# LARIX_V5.net
KiCad netlist of a schematic drawn in EAGLE
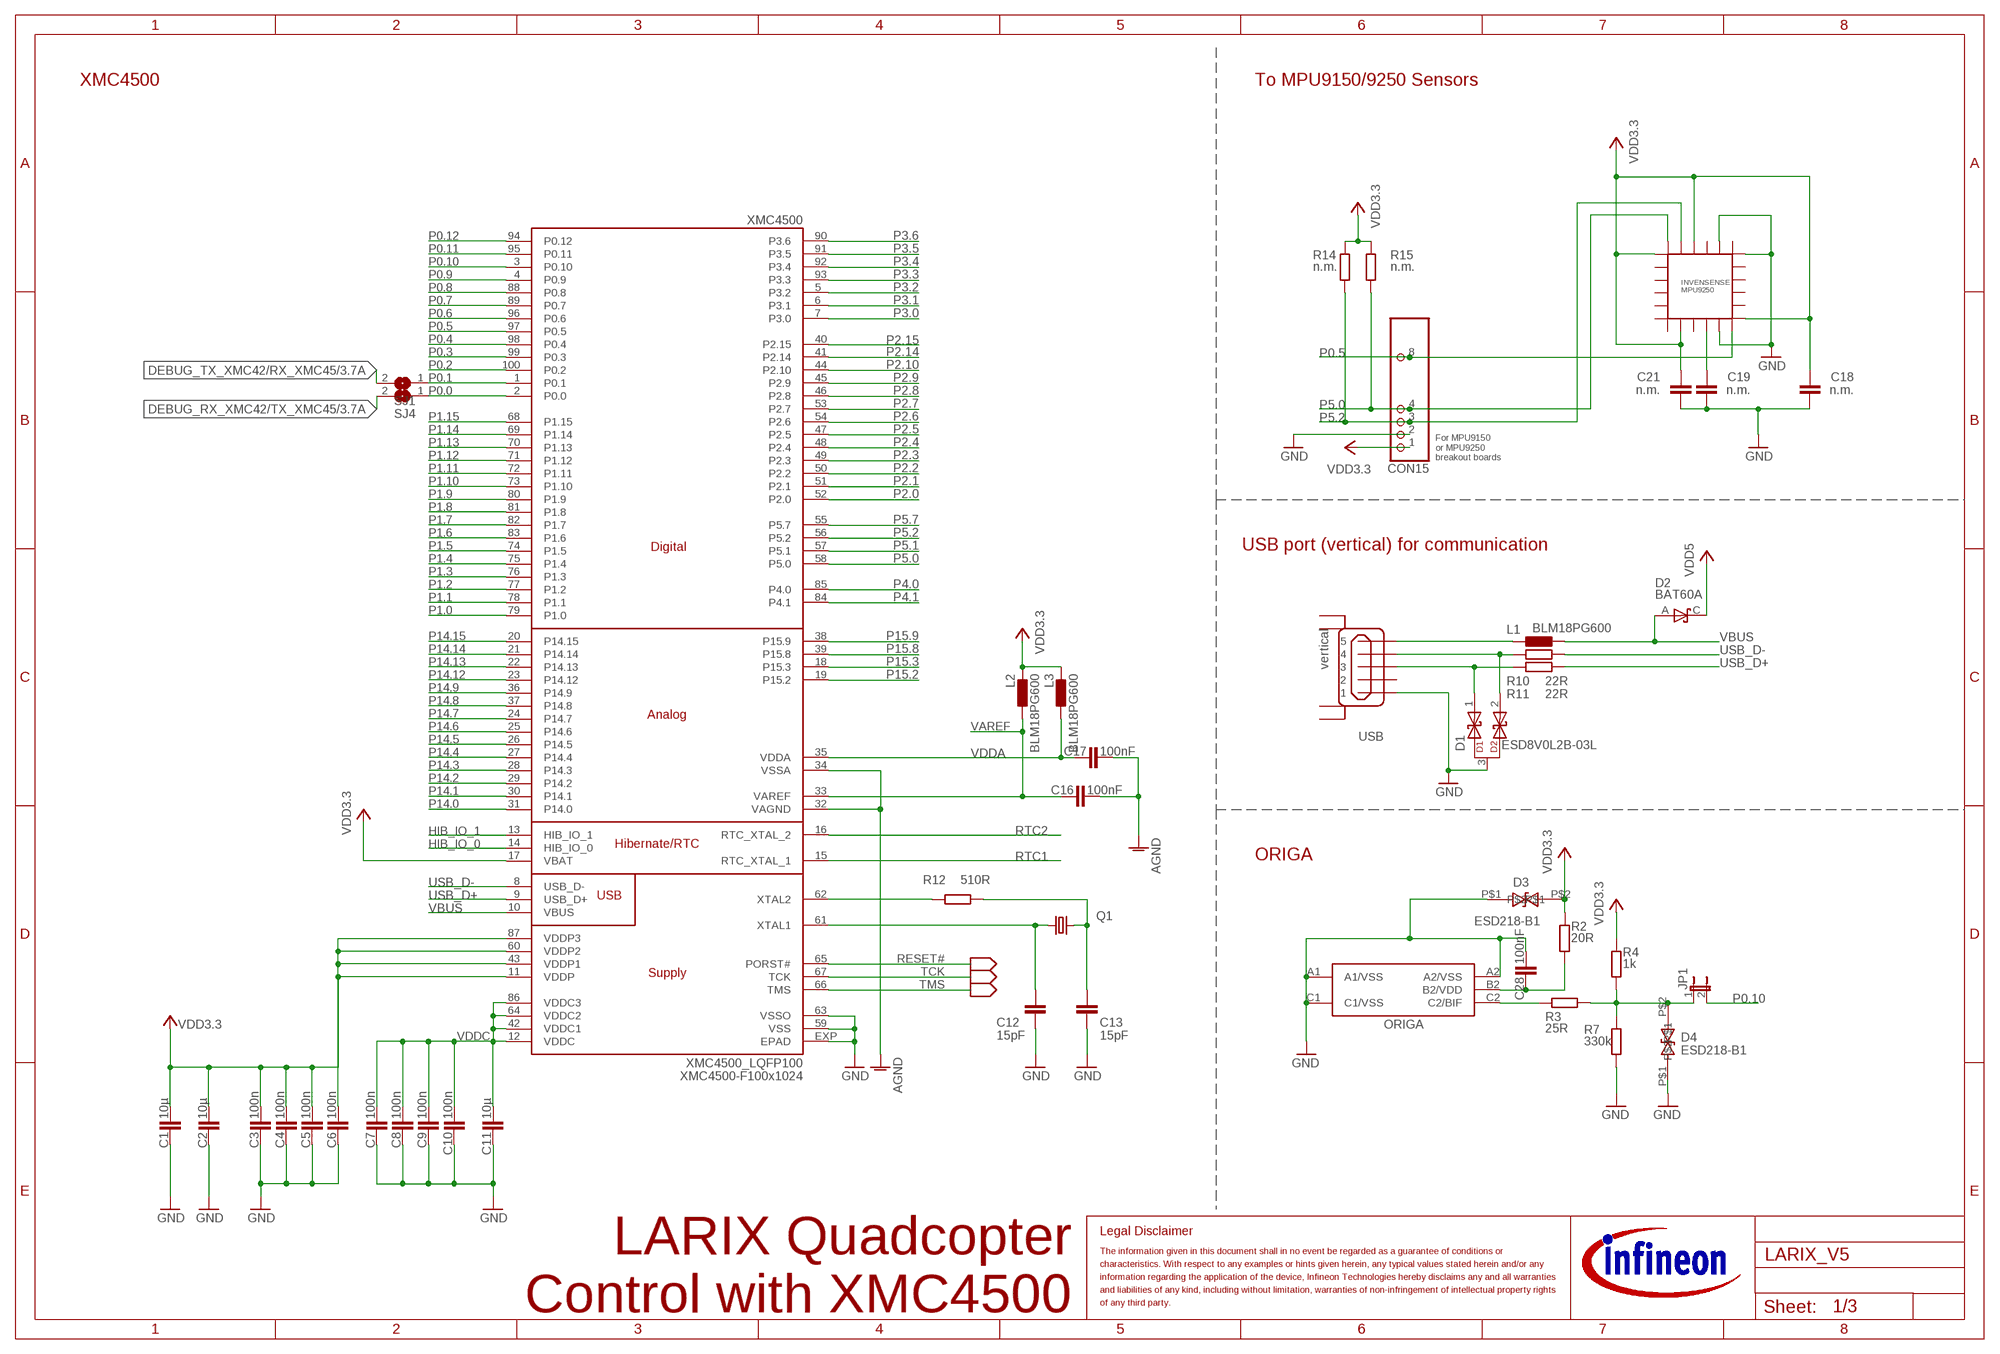
[diagram p0: schematic, sheet 1]
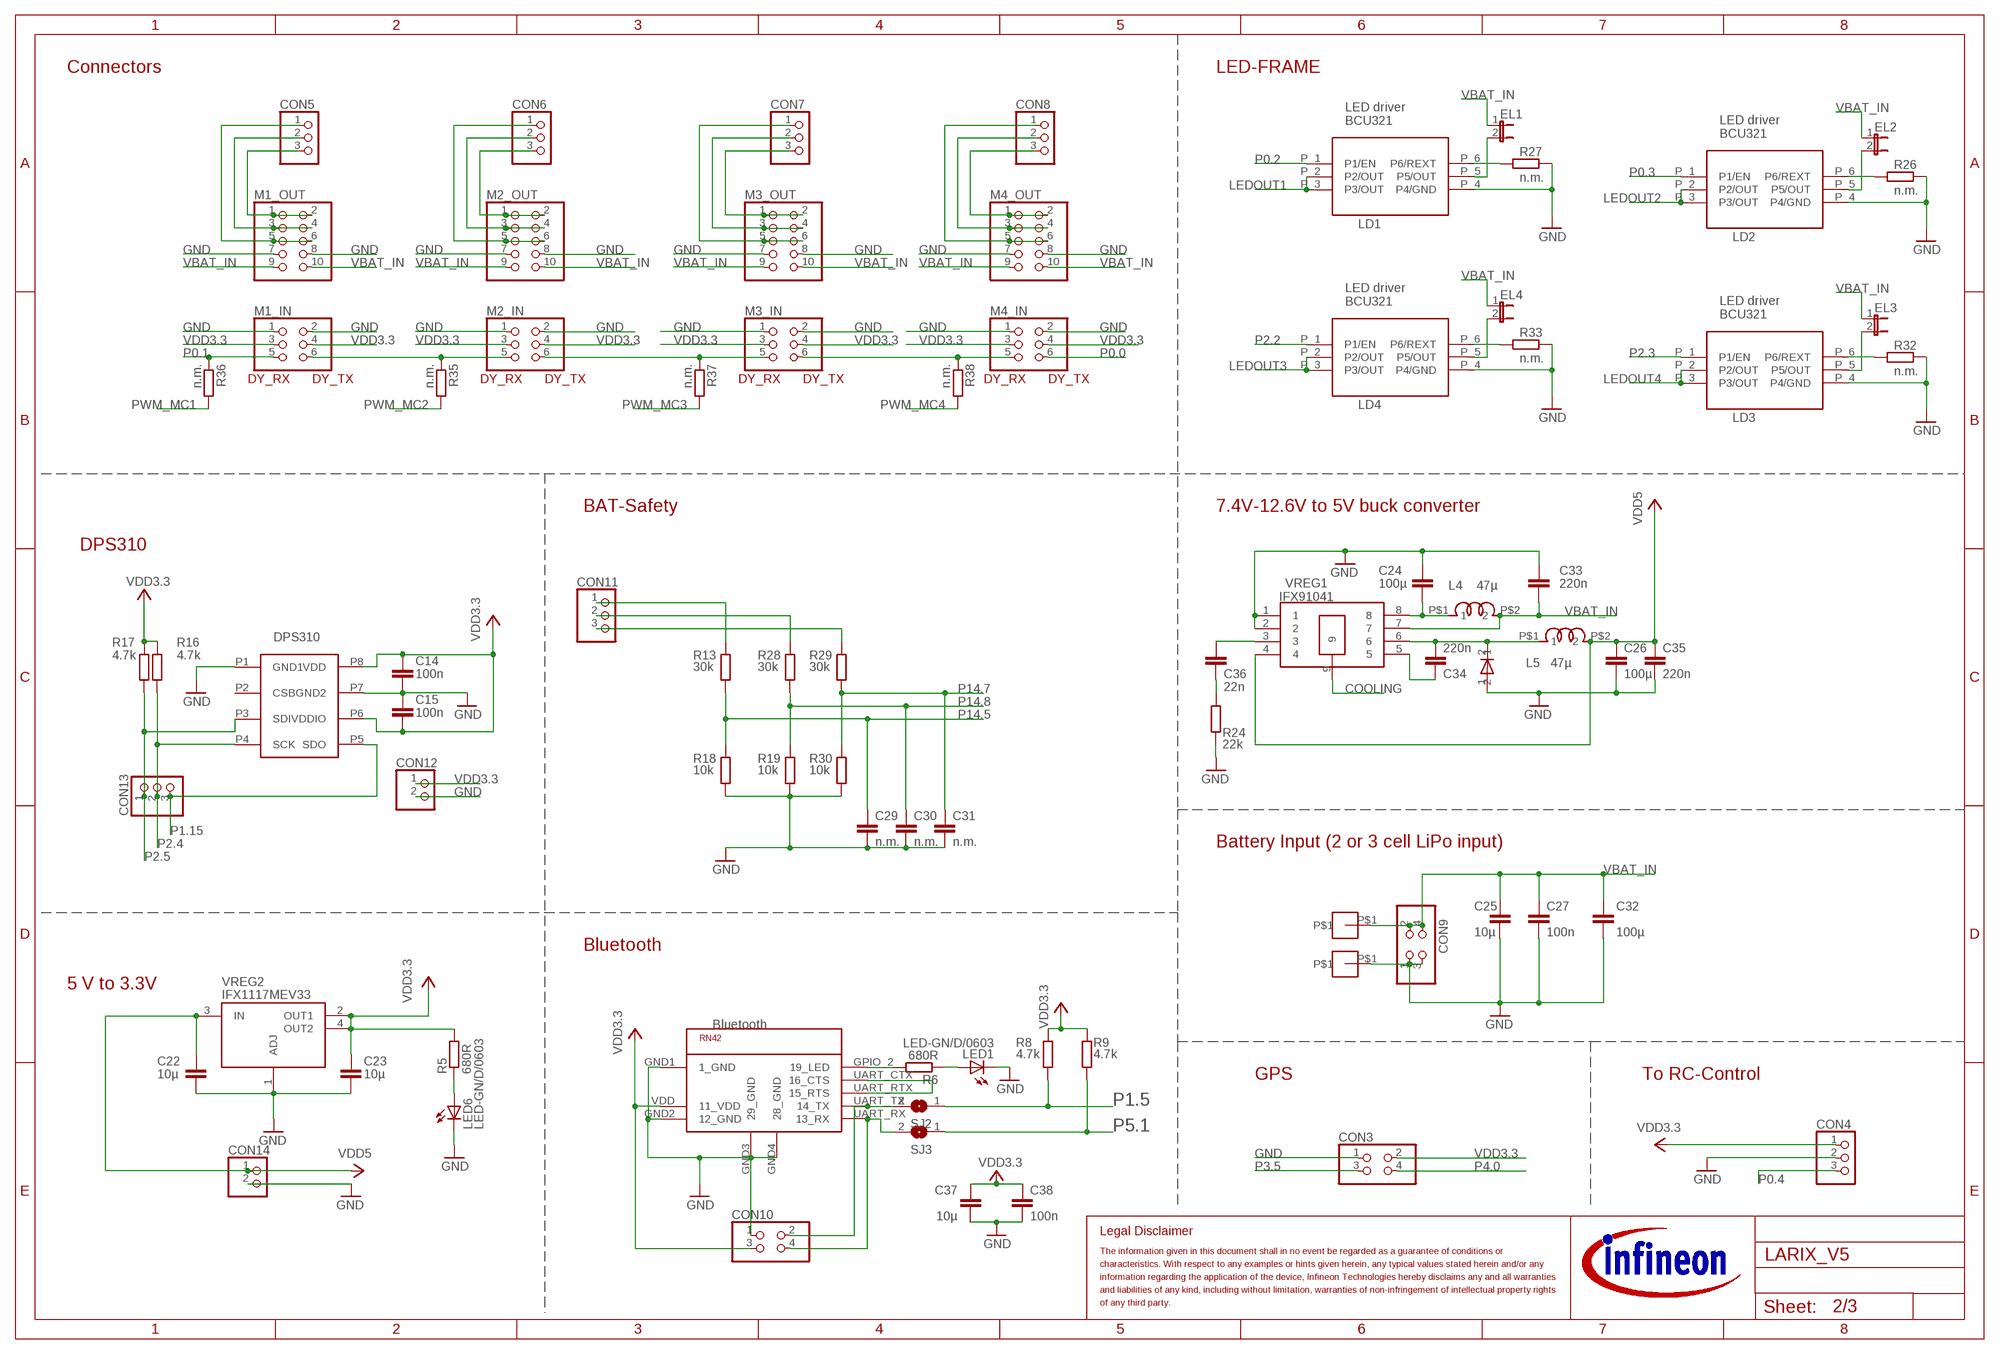
[diagram p1: schematic, sheet 2]
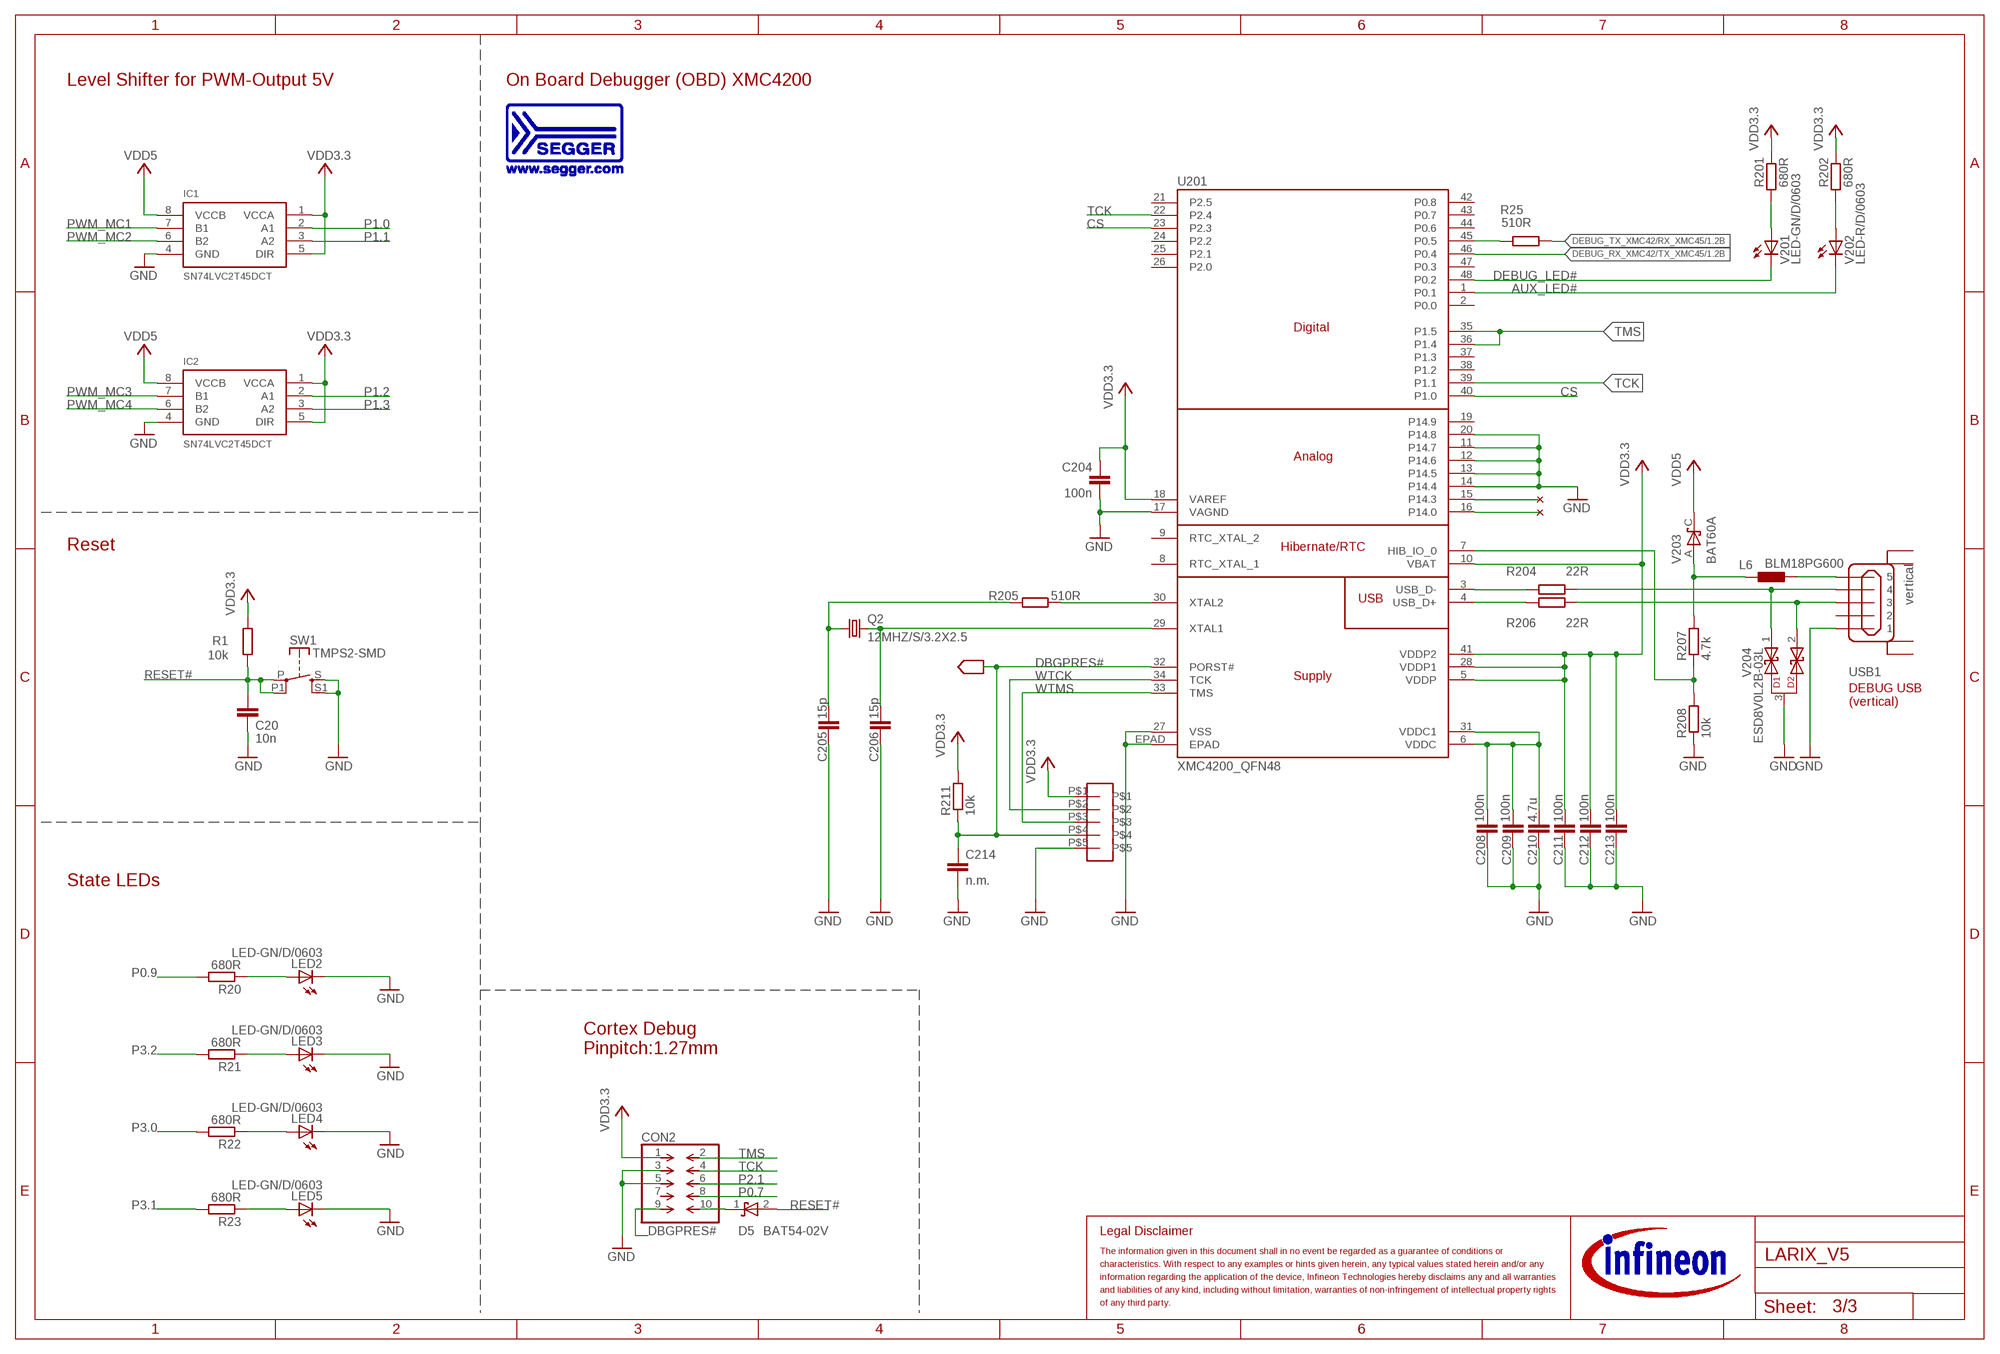
[diagram p2: schematic, sheet 3]

(export (version "E")
  (design (tool "Eeschema 10.0.6"))
  (components
    (comp (ref "C1")
      (value "10µ")
      (footprint "eagle-import:C0805K")
      (libsource (lib "eagle-import") (part "C-EUC0805K"))
    )
    (comp (ref "C2")
      (value "10µ")
      (footprint "eagle-import:C0805K")
      (libsource (lib "eagle-import") (part "C-EUC0805K"))
    )
    (comp (ref "C3")
      (value "100n")
      (footprint "eagle-import:C0603")
      (libsource (lib "eagle-import") (part "resistor_C-EUC0603"))
    )
    (comp (ref "C4")
      (value "100n")
      (footprint "eagle-import:C0603")
      (libsource (lib "eagle-import") (part "resistor_C-EUC0603"))
    )
    (comp (ref "C5")
      (value "100n")
      (footprint "eagle-import:C0603")
      (libsource (lib "eagle-import") (part "resistor_C-EUC0603"))
    )
    (comp (ref "C6")
      (value "100n")
      (footprint "eagle-import:C0603")
      (libsource (lib "eagle-import") (part "resistor_C-EUC0603"))
    )
    (comp (ref "C7")
      (value "100n")
      (footprint "eagle-import:C0603")
      (libsource (lib "eagle-import") (part "resistor_C-EUC0603"))
    )
    (comp (ref "C8")
      (value "100n")
      (footprint "eagle-import:C0603")
      (libsource (lib "eagle-import") (part "resistor_C-EUC0603"))
    )
    (comp (ref "C9")
      (value "100n")
      (footprint "eagle-import:C0603")
      (libsource (lib "eagle-import") (part "resistor_C-EUC0603"))
    )
    (comp (ref "C10")
      (value "100n")
      (footprint "eagle-import:C0603")
      (libsource (lib "eagle-import") (part "resistor_C-EUC0603"))
    )
    (comp (ref "C11")
      (value "10µ")
      (footprint "eagle-import:C0805K")
      (libsource (lib "eagle-import") (part "C-EUC0805K"))
    )
    (comp (ref "C12")
      (value "15pF")
      (footprint "eagle-import:C0603")
      (libsource (lib "eagle-import") (part "resistor_C-EUC0603"))
    )
    (comp (ref "C13")
      (value "15pF")
      (footprint "eagle-import:C0603")
      (libsource (lib "eagle-import") (part "resistor_C-EUC0603"))
    )
    (comp (ref "C16")
      (value "100nF")
      (footprint "eagle-import:C0603")
      (libsource (lib "eagle-import") (part "resistor_C-EUC0603"))
    )
    (comp (ref "C17")
      (value "100nF")
      (footprint "eagle-import:C0603")
      (libsource (lib "eagle-import") (part "resistor_C-EUC0603"))
    )
    (comp (ref "C18")
      (value "n.m.")
      (footprint "eagle-import:C0603")
      (libsource (lib "eagle-import") (part "resistor_C-EUC0603"))
    )
    (comp (ref "C19")
      (value "n.m.")
      (footprint "eagle-import:C0603")
      (libsource (lib "eagle-import") (part "resistor_C-EUC0603"))
    )
    (comp (ref "C21")
      (value "n.m.")
      (footprint "eagle-import:C0603")
      (libsource (lib "eagle-import") (part "resistor_C-EUC0603"))
    )
    (comp (ref "C28")
      (value "100nF")
      (footprint "eagle-import:C0603")
      (libsource (lib "eagle-import") (part "resistor_C-EUC0603"))
    )
    (comp (ref "CON15")
      (value "PINHD-1X10")
      (footprint "eagle-import:1X10")
      (libsource (lib "eagle-import") (part "PINHD-1X10"))
    )
    (comp (ref "D1")
      (value "ESD8V0L2B-03L")
      (footprint "eagle-import:TSLP-3-1")
      (libsource (lib "eagle-import") (part "ESD8V0L2B-03L"))
    )
    (comp (ref "D2")
      (value "BAT60A")
      (footprint "eagle-import:SOD323-R")
      (libsource (lib "eagle-import") (part "XMC4500_Relax-V1+USBvertical_BAT60"))
    )
    (comp (ref "D3")
      (value "ESD218-B1-02EL")
      (footprint "eagle-import:TSLP-2-20")
      (libsource (lib "eagle-import") (part "ESD218-B1-02EL"))
    )
    (comp (ref "D4")
      (value "ESD218-B1-02EL")
      (footprint "eagle-import:TSLP-2-20")
      (libsource (lib "eagle-import") (part "ESD218-B1-02EL"))
    )
    (comp (ref "JP1")
      (value "JP1E")
      (footprint "eagle-import:JP1")
      (libsource (lib "eagle-import") (part "JP1E"))
    )
    (comp (ref "L1")
      (value "BLM18PG600")
      (footprint "eagle-import:L1608")
      (libsource (lib "eagle-import") (part "L_EU_L0603"))
    )
    (comp (ref "L2")
      (value "BLM18PG600")
      (footprint "eagle-import:L1608")
      (libsource (lib "eagle-import") (part "L_EU_L0603"))
    )
    (comp (ref "L3")
      (value "BLM18PG600")
      (footprint "eagle-import:L1608")
      (libsource (lib "eagle-import") (part "L_EU_L0603"))
    )
    (comp (ref "MPU9250")
      (value "INVENSENSE9250EHERBY")
      (footprint "eagle-import:QFN3X3-24+")
      (libsource (lib "eagle-import") (part "INVENSENSE9250HERBYE"))
    )
    (comp (ref "ORIGA")
      (value "ORIGA2L")
      (footprint "eagle-import:WLB-5")
      (libsource (lib "eagle-import") (part "ORIGA2L"))
    )
    (comp (ref "Q1")
      (value "12MHZ/S/3.2X2.5")
      (footprint "eagle-import:32X25_4PAD")
      (libsource (lib "eagle-import") (part "NX3225_2"))
    )
    (comp (ref "R2")
      (value "20R")
      (footprint "eagle-import:R0603")
      (libsource (lib "eagle-import") (part "R-EU_R0603"))
    )
    (comp (ref "R3")
      (value "25R")
      (footprint "eagle-import:R0603")
      (libsource (lib "eagle-import") (part "R-EU_R0603"))
    )
    (comp (ref "R4")
      (value "1k")
      (footprint "eagle-import:R0603")
      (libsource (lib "eagle-import") (part "R-EU_R0603"))
    )
    (comp (ref "R7")
      (value "330k")
      (footprint "eagle-import:R0603")
      (libsource (lib "eagle-import") (part "R-EU_R0603"))
    )
    (comp (ref "R10")
      (value "22R")
      (footprint "eagle-import:R0603")
      (libsource (lib "eagle-import") (part "resistor_R-EU_R0603"))
    )
    (comp (ref "R11")
      (value "22R")
      (footprint "eagle-import:R0603")
      (libsource (lib "eagle-import") (part "resistor_R-EU_R0603"))
    )
    (comp (ref "R12")
      (value "510R")
      (footprint "eagle-import:R0603")
      (libsource (lib "eagle-import") (part "R-EU_R0603"))
    )
    (comp (ref "R14")
      (value "n.m.")
      (footprint "eagle-import:R0603")
      (libsource (lib "eagle-import") (part "resistor_R-EU_R0603"))
    )
    (comp (ref "R15")
      (value "n.m.")
      (footprint "eagle-import:R0603")
      (libsource (lib "eagle-import") (part "resistor_R-EU_R0603"))
    )
    (comp (ref "SJ1") (value "SJ") (footprint "eagle-import:SJ") (libsource (lib "eagle-import") (part "SJ")))
    (comp (ref "SJ4") (value "SJ") (footprint "eagle-import:SJ") (libsource (lib "eagle-import") (part "SJ")))
    (comp (ref "USB")
      (value "vertical")
      (footprint "eagle-import:USBVERTICAL")
      (libsource (lib "eagle-import") (part "MICRO_USB_VERTICAL"))
    )
    (comp (ref "XMC4500")
      (value "XMC4500_LQFP100")
      (footprint "eagle-import:P_PG-LQFP-100-11")
      (libsource (lib "eagle-import") (part "XMC4400_LQFP100"))
    )
    (comp (ref "C14")
      (value "100n")
      (footprint "eagle-import:C0603")
      (libsource (lib "eagle-import") (part "resistor_C-EUC0603"))
    )
    (comp (ref "C15")
      (value "100n")
      (footprint "eagle-import:C0603")
      (libsource (lib "eagle-import") (part "resistor_C-EUC0603"))
    )
    (comp (ref "C22")
      (value "10µ")
      (footprint "eagle-import:C0805K")
      (libsource (lib "eagle-import") (part "C-EUC0805K"))
    )
    (comp (ref "C23")
      (value "10µ")
      (footprint "eagle-import:C0805K")
      (libsource (lib "eagle-import") (part "C-EUC0805K"))
    )
    (comp (ref "C24")
      (value "100µ")
      (footprint "eagle-import:C1210")
      (libsource (lib "eagle-import") (part "resistor_C-EUC1210"))
    )
    (comp (ref "C25")
      (value "10µ")
      (footprint "eagle-import:C0805K")
      (libsource (lib "eagle-import") (part "C-EUC0805K"))
    )
    (comp (ref "C26")
      (value "100µ")
      (footprint "eagle-import:C1210")
      (libsource (lib "eagle-import") (part "resistor_C-EUC1210"))
    )
    (comp (ref "C27")
      (value "100n")
      (footprint "eagle-import:C0603")
      (libsource (lib "eagle-import") (part "resistor_C-EUC0603"))
    )
    (comp (ref "C29")
      (value "n.m.")
      (footprint "eagle-import:C0603")
      (libsource (lib "eagle-import") (part "resistor_C-EUC0603"))
    )
    (comp (ref "C30")
      (value "n.m.")
      (footprint "eagle-import:C0603")
      (libsource (lib "eagle-import") (part "resistor_C-EUC0603"))
    )
    (comp (ref "C31")
      (value "n.m.")
      (footprint "eagle-import:C0603")
      (libsource (lib "eagle-import") (part "resistor_C-EUC0603"))
    )
    (comp (ref "C32")
      (value "100µ")
      (footprint "eagle-import:C1210")
      (libsource (lib "eagle-import") (part "resistor_C-EUC1210"))
    )
    (comp (ref "C33")
      (value "220n")
      (footprint "eagle-import:C0603")
      (libsource (lib "eagle-import") (part "resistor_C-EUC0603"))
    )
    (comp (ref "C34")
      (value "220n")
      (footprint "eagle-import:C0603")
      (libsource (lib "eagle-import") (part "resistor_C-EUC0603"))
    )
    (comp (ref "C35")
      (value "220n")
      (footprint "eagle-import:C0603")
      (libsource (lib "eagle-import") (part "resistor_C-EUC0603"))
    )
    (comp (ref "C36")
      (value "22n")
      (footprint "eagle-import:C0603")
      (libsource (lib "eagle-import") (part "resistor_C-EUC0603"))
    )
    (comp (ref "C37")
      (value "10µ")
      (footprint "eagle-import:C0805K")
      (libsource (lib "eagle-import") (part "C-EUC0805K"))
    )
    (comp (ref "C38")
      (value "100n")
      (footprint "eagle-import:C0603")
      (libsource (lib "eagle-import") (part "resistor_C-EUC0603"))
    )
    (comp (ref "CON3")
      (value "PINHD-2X2")
      (footprint "eagle-import:2X02")
      (libsource (lib "eagle-import") (part "PINHD-2X2"))
    )
    (comp (ref "CON4")
      (value "PINHD-1X3")
      (footprint "eagle-import:1X03")
      (libsource (lib "eagle-import") (part "PINHD-1X3"))
    )
    (comp (ref "CON5")
      (value "PINHD-1X3")
      (footprint "eagle-import:1X03")
      (libsource (lib "eagle-import") (part "PINHD-1X3"))
    )
    (comp (ref "CON6")
      (value "PINHD-1X3")
      (footprint "eagle-import:1X03")
      (libsource (lib "eagle-import") (part "PINHD-1X3"))
    )
    (comp (ref "CON7")
      (value "PINHD-1X3")
      (footprint "eagle-import:1X03")
      (libsource (lib "eagle-import") (part "PINHD-1X3"))
    )
    (comp (ref "CON8")
      (value "PINHD-1X3")
      (footprint "eagle-import:1X03")
      (libsource (lib "eagle-import") (part "PINHD-1X3"))
    )
    (comp (ref "CON9")
      (value "PINHD-2X2")
      (footprint "eagle-import:2X02")
      (libsource (lib "eagle-import") (part "PINHD-2X2"))
    )
    (comp (ref "CON10")
      (value "PINHD-2X2")
      (footprint "eagle-import:2X02")
      (libsource (lib "eagle-import") (part "PINHD-2X2"))
    )
    (comp (ref "CON11")
      (value "PINHD-1X3")
      (footprint "eagle-import:1X03")
      (libsource (lib "eagle-import") (part "PINHD-1X3"))
    )
    (comp (ref "CON12")
      (value "PINHD-1X2")
      (footprint "eagle-import:1X02")
      (libsource (lib "eagle-import") (part "PINHD-1X2"))
    )
    (comp (ref "CON13")
      (value "PINHD-1X3")
      (footprint "eagle-import:1X03")
      (libsource (lib "eagle-import") (part "PINHD-1X3"))
    )
    (comp (ref "CON14")
      (value "PINHD-1X2")
      (footprint "eagle-import:1X02")
      (libsource (lib "eagle-import") (part "PINHD-1X2"))
    )
    (comp (ref "D6")
      (value "BAS21-03W")
      (footprint "eagle-import:INF-SOD323_V_1PRIMARY")
      (libsource (lib "eagle-import") (part "INF-SOD323_V_1"))
    )
    (comp (ref "DPS310")
      (value "DPS310DRUCKSENSOR")
      (footprint "eagle-import:LGA8R125P0X4_500X300X120")
      (libsource (lib "eagle-import") (part "DPS310DRUCKSENSOR"))
    )
    (comp (ref "EL1")
      (value "JP1E")
      (footprint "eagle-import:JP1")
      (libsource (lib "eagle-import") (part "JP1E"))
    )
    (comp (ref "EL2")
      (value "JP1E")
      (footprint "eagle-import:JP1")
      (libsource (lib "eagle-import") (part "JP1E"))
    )
    (comp (ref "EL3")
      (value "JP1E")
      (footprint "eagle-import:JP1")
      (libsource (lib "eagle-import") (part "JP1E"))
    )
    (comp (ref "EL4")
      (value "JP1E")
      (footprint "eagle-import:JP1")
      (libsource (lib "eagle-import") (part "JP1E"))
    )
    (comp (ref "L4")
      (value "47µH")
      (footprint "eagle-import:WE-TPC")
      (libsource (lib "eagle-import") (part "WUERTH47UHIND"))
    )
    (comp (ref "L5")
      (value "47µH")
      (footprint "eagle-import:WE-TPC")
      (libsource (lib "eagle-import") (part "WUERTH47UHIND"))
    )
    (comp (ref "LD1")
      (value "BCU321")
      (footprint "eagle-import:SC74")
      (libsource (lib "eagle-import") (part "BCU320"))
    )
    (comp (ref "LD2")
      (value "BCU321")
      (footprint "eagle-import:SC74")
      (libsource (lib "eagle-import") (part "BCU320"))
    )
    (comp (ref "LD3")
      (value "BCU321")
      (footprint "eagle-import:SC74")
      (libsource (lib "eagle-import") (part "BCU320"))
    )
    (comp (ref "LD4")
      (value "BCU321")
      (footprint "eagle-import:SC74")
      (libsource (lib "eagle-import") (part "BCU320"))
    )
    (comp (ref "LED1")
      (value "LED-GN/D/0603")
      (footprint "eagle-import:CHIPLED_0603")
      (libsource (lib "eagle-import") (part "LEDCHIPLED_0603"))
    )
    (comp (ref "LED6")
      (value "LED-GN/D/0603")
      (footprint "eagle-import:CHIPLED_0603")
      (libsource (lib "eagle-import") (part "led_LEDCHIPLED_0603"))
    )
    (comp (ref "M1_IN")
      (value "PINHD-2X3")
      (footprint "eagle-import:2X03")
      (libsource (lib "eagle-import") (part "PINHD-2X3"))
    )
    (comp (ref "M1_OUT")
      (value "PINHD-2X5")
      (footprint "eagle-import:2X05")
      (libsource (lib "eagle-import") (part "PINHD-2X5"))
    )
    (comp (ref "M2_IN")
      (value "PINHD-2X3")
      (footprint "eagle-import:2X03")
      (libsource (lib "eagle-import") (part "PINHD-2X3"))
    )
    (comp (ref "M2_OUT")
      (value "PINHD-2X5")
      (footprint "eagle-import:2X05")
      (libsource (lib "eagle-import") (part "PINHD-2X5"))
    )
    (comp (ref "M3_IN")
      (value "PINHD-2X3")
      (footprint "eagle-import:2X03")
      (libsource (lib "eagle-import") (part "PINHD-2X3"))
    )
    (comp (ref "M3_OUT")
      (value "PINHD-2X5")
      (footprint "eagle-import:2X05")
      (libsource (lib "eagle-import") (part "PINHD-2X5"))
    )
    (comp (ref "M4_IN")
      (value "PINHD-2X3")
      (footprint "eagle-import:2X03")
      (libsource (lib "eagle-import") (part "PINHD-2X3"))
    )
    (comp (ref "M4_OUT")
      (value "PINHD-2X5")
      (footprint "eagle-import:2X05")
      (libsource (lib "eagle-import") (part "PINHD-2X5"))
    )
    (comp (ref "PAD1")
      (value "PAD-BATTERY")
      (footprint "eagle-import:BATT-SOLDER")
      (libsource (lib "eagle-import") (part "PAD-BATTERY"))
    )
    (comp (ref "PAD2")
      (value "PAD-BATTERY")
      (footprint "eagle-import:BATT-SOLDER")
      (libsource (lib "eagle-import") (part "PAD-BATTERY"))
    )
    (comp (ref "R5")
      (value "680R")
      (footprint "eagle-import:R0603")
      (libsource (lib "eagle-import") (part "R-EU_R0603"))
    )
    (comp (ref "R6")
      (value "680R")
      (footprint "eagle-import:R0603")
      (libsource (lib "eagle-import") (part "R-EU_R0603"))
    )
    (comp (ref "R8")
      (value "4.7k")
      (footprint "eagle-import:R0603")
      (libsource (lib "eagle-import") (part "R-EU_R0603"))
    )
    (comp (ref "R9")
      (value "4.7k")
      (footprint "eagle-import:R0603")
      (libsource (lib "eagle-import") (part "R-EU_R0603"))
    )
    (comp (ref "R13")
      (value "30k")
      (footprint "eagle-import:R0603")
      (libsource (lib "eagle-import") (part "R-EU_R0603"))
    )
    (comp (ref "R16")
      (value "4.7k")
      (footprint "eagle-import:R0603")
      (libsource (lib "eagle-import") (part "resistor_R-EU_R0603"))
    )
    (comp (ref "R17")
      (value "4.7k")
      (footprint "eagle-import:R0603")
      (libsource (lib "eagle-import") (part "resistor_R-EU_R0603"))
    )
    (comp (ref "R18")
      (value "10k")
      (footprint "eagle-import:R0603")
      (libsource (lib "eagle-import") (part "R-EU_R0603"))
    )
    (comp (ref "R19")
      (value "10k")
      (footprint "eagle-import:R0603")
      (libsource (lib "eagle-import") (part "R-EU_R0603"))
    )
    (comp (ref "R24")
      (value "22k")
      (footprint "eagle-import:R0603")
      (libsource (lib "eagle-import") (part "R-EU_R0603"))
    )
    (comp (ref "R26")
      (value "n.m.")
      (footprint "eagle-import:R0603")
      (libsource (lib "eagle-import") (part "resistor_R-EU_R0603"))
    )
    (comp (ref "R27")
      (value "n.m.")
      (footprint "eagle-import:R0603")
      (libsource (lib "eagle-import") (part "resistor_R-EU_R0603"))
    )
    (comp (ref "R28")
      (value "30k")
      (footprint "eagle-import:R0603")
      (libsource (lib "eagle-import") (part "R-EU_R0603"))
    )
    (comp (ref "R29")
      (value "30k")
      (footprint "eagle-import:R0603")
      (libsource (lib "eagle-import") (part "R-EU_R0603"))
    )
    (comp (ref "R30")
      (value "10k")
      (footprint "eagle-import:R0603")
      (libsource (lib "eagle-import") (part "R-EU_R0603"))
    )
    (comp (ref "R32")
      (value "n.m.")
      (footprint "eagle-import:R0603")
      (libsource (lib "eagle-import") (part "resistor_R-EU_R0603"))
    )
    (comp (ref "R33")
      (value "n.m.")
      (footprint "eagle-import:R0603")
      (libsource (lib "eagle-import") (part "resistor_R-EU_R0603"))
    )
    (comp (ref "R35")
      (value "n.m.")
      (footprint "eagle-import:R0603")
      (libsource (lib "eagle-import") (part "R-EU_R0603"))
    )
    (comp (ref "R36")
      (value "n.m.")
      (footprint "eagle-import:R0603")
      (libsource (lib "eagle-import") (part "R-EU_R0603"))
    )
    (comp (ref "R37")
      (value "n.m.")
      (footprint "eagle-import:R0603")
      (libsource (lib "eagle-import") (part "R-EU_R0603"))
    )
    (comp (ref "R38")
      (value "n.m.")
      (footprint "eagle-import:R0603")
      (libsource (lib "eagle-import") (part "R-EU_R0603"))
    )
    (comp (ref "RN42")
      (value "BLUETOOTHRN42+SHIELD")
      (footprint "eagle-import:RN42+SHIELD")
      (libsource (lib "eagle-import") (part "BLUETOOTHRN42+SHIELD"))
    )
    (comp (ref "SJ2") (value "SJ") (footprint "eagle-import:SJ") (libsource (lib "eagle-import") (part "SJ")))
    (comp (ref "SJ3") (value "SJ") (footprint "eagle-import:SJ") (libsource (lib "eagle-import") (part "SJ")))
    (comp (ref "VREG1")
      (value "INF-PG-DSO-8-27_N_1")
      (footprint "eagle-import:INF-PG-DSO-8-27_N_1PRIMARY")
      (libsource (lib "eagle-import") (part "INF-PG-DSO-8-27_N_1"))
    )
    (comp (ref "VREG2")
      (value "IFX1117MEV33")
      (footprint "eagle-import:SOT223")
      (libsource (lib "eagle-import") (part "IFX1117"))
    )
    (comp (ref "C20")
      (value "10n")
      (footprint "eagle-import:C0603")
      (libsource (lib "eagle-import") (part "resistor_C-EUC0603"))
    )
    (comp (ref "C204")
      (value "100n")
      (footprint "eagle-import:C0402")
      (libsource (lib "eagle-import") (part "C-EUC0402"))
    )
    (comp (ref "C205")
      (value "15p")
      (footprint "eagle-import:C0402")
      (libsource (lib "eagle-import") (part "C-EUC0402"))
    )
    (comp (ref "C206")
      (value "15p")
      (footprint "eagle-import:C0402")
      (libsource (lib "eagle-import") (part "C-EUC0402"))
    )
    (comp (ref "C208")
      (value "100n")
      (footprint "eagle-import:C0402")
      (libsource (lib "eagle-import") (part "C-EUC0402"))
    )
    (comp (ref "C209")
      (value "100n")
      (footprint "eagle-import:C0402")
      (libsource (lib "eagle-import") (part "C-EUC0402"))
    )
    (comp (ref "C210")
      (value "4.7u")
      (footprint "eagle-import:C0805K")
      (libsource (lib "eagle-import") (part "C-EUC0805K"))
    )
    (comp (ref "C211")
      (value "100n")
      (footprint "eagle-import:C0402")
      (libsource (lib "eagle-import") (part "C-EUC0402"))
    )
    (comp (ref "C212")
      (value "100n")
      (footprint "eagle-import:C0402")
      (libsource (lib "eagle-import") (part "C-EUC0402"))
    )
    (comp (ref "C213")
      (value "100n")
      (footprint "eagle-import:C0402")
      (libsource (lib "eagle-import") (part "C-EUC0402"))
    )
    (comp (ref "C214")
      (value "n.m.")
      (footprint "eagle-import:C0402")
      (libsource (lib "eagle-import") (part "C-EUC0402"))
    )
    (comp (ref "CON2")
      (value "FTSH-105-01-F-D-K")
      (footprint "eagle-import:FTSH-105-01-F-D-K")
      (libsource (lib "eagle-import") (part "FTSH-105-01-F-D-K"))
    )
    (comp (ref "D5")
      (value "BAT54-02V")
      (footprint "eagle-import:SC79")
      (libsource (lib "eagle-import") (part "BAT54-02V"))
    )
    (comp (ref "IC1")
      (value "SN74LVC2T45DCT")
      (footprint "eagle-import:DCT_R-PDSO-G8")
      (libsource (lib "eagle-import") (part "SN74LVC2T45DCT"))
    )
    (comp (ref "IC2")
      (value "SN74LVC2T45DCT")
      (footprint "eagle-import:DCT_R-PDSO-G8")
      (libsource (lib "eagle-import") (part "SN74LVC2T45DCT"))
    )
    (comp (ref "L6")
      (value "BLM18PG600")
      (footprint "eagle-import:L1608")
      (libsource (lib "eagle-import") (part "L_EU_L0603"))
    )
    (comp (ref "LED2")
      (value "LED-GN/D/0603")
      (footprint "eagle-import:CHIPLED_0603")
      (libsource (lib "eagle-import") (part "led_LEDCHIPLED_0603"))
    )
    (comp (ref "LED3")
      (value "LED-GN/D/0603")
      (footprint "eagle-import:CHIPLED_0603")
      (libsource (lib "eagle-import") (part "led_LEDCHIPLED_0603"))
    )
    (comp (ref "LED4")
      (value "LED-GN/D/0603")
      (footprint "eagle-import:CHIPLED_0603")
      (libsource (lib "eagle-import") (part "led_LEDCHIPLED_0603"))
    )
    (comp (ref "LED5")
      (value "LED-GN/D/0603")
      (footprint "eagle-import:CHIPLED_0603")
      (libsource (lib "eagle-import") (part "led_LEDCHIPLED_0603"))
    )
    (comp (ref "Q2")
      (value "12MHZ/S/3.2X2.5")
      (footprint "eagle-import:32X25_4PAD")
      (libsource (lib "eagle-import") (part "XMC4700_Relax-V1_NX3225_2"))
    )
    (comp (ref "R1")
      (value "10k")
      (footprint "eagle-import:R0603")
      (libsource (lib "eagle-import") (part "resistor_R-EU_R0603"))
    )
    (comp (ref "R20")
      (value "680R")
      (footprint "eagle-import:R0603")
      (libsource (lib "eagle-import") (part "R-EU_R0603"))
    )
    (comp (ref "R21")
      (value "680R")
      (footprint "eagle-import:R0603")
      (libsource (lib "eagle-import") (part "R-EU_R0603"))
    )
    (comp (ref "R22")
      (value "680R")
      (footprint "eagle-import:R0603")
      (libsource (lib "eagle-import") (part "R-EU_R0603"))
    )
    (comp (ref "R23")
      (value "680R")
      (footprint "eagle-import:R0603")
      (libsource (lib "eagle-import") (part "R-EU_R0603"))
    )
    (comp (ref "R25")
      (value "510R")
      (footprint "eagle-import:R0402")
      (libsource (lib "eagle-import") (part "R-EU_R0402"))
    )
    (comp (ref "R201")
      (value "680R")
      (footprint "eagle-import:R0603")
      (libsource (lib "eagle-import") (part "R-EU_R0603"))
    )
    (comp (ref "R202")
      (value "680R")
      (footprint "eagle-import:R0603")
      (libsource (lib "eagle-import") (part "R-EU_R0603"))
    )
    (comp (ref "R204")
      (value "22R")
      (footprint "eagle-import:R0402")
      (libsource (lib "eagle-import") (part "R-EU_R0402"))
    )
    (comp (ref "R205")
      (value "510R")
      (footprint "eagle-import:R0603")
      (libsource (lib "eagle-import") (part "R-EU_R0603"))
    )
    (comp (ref "R206")
      (value "22R")
      (footprint "eagle-import:R0402")
      (libsource (lib "eagle-import") (part "R-EU_R0402"))
    )
    (comp (ref "R207")
      (value "4.7k")
      (footprint "eagle-import:R0402")
      (libsource (lib "eagle-import") (part "R-EU_R0402"))
    )
    (comp (ref "R208")
      (value "10k")
      (footprint "eagle-import:R0402")
      (libsource (lib "eagle-import") (part "R-EU_R0402"))
    )
    (comp (ref "R211")
      (value "10k")
      (footprint "eagle-import:R0402")
      (libsource (lib "eagle-import") (part "R-EU_R0402"))
    )
    (comp (ref "SW1")
      (value "TMPS2-SMD")
      (footprint "eagle-import:FSM2JSMA")
      (libsource (lib "eagle-import") (part "FSM2JSMA"))
    )
    (comp (ref "U$9")
      (value "127MARKED")
      (footprint "eagle-import:PINHEAD_127")
      (libsource (lib "eagle-import") (part "127MARKED"))
    )
    (comp (ref "U$11")
      (value "SEGGER.L_100")
      (footprint "eagle-import:LOGO_100")
      (libsource (lib "eagle-import") (part "SEGGER.L_100"))
    )
    (comp (ref "U201")
      (value "XMC4200_QFN48")
      (footprint "eagle-import:QFN-48-7X7")
      (libsource (lib "eagle-import") (part "XMC4200_QFN48"))
    )
    (comp (ref "USB1")
      (value "vertical")
      (footprint "eagle-import:USBVERTICAL")
      (libsource (lib "eagle-import") (part "MICRO_USB_VERTICAL"))
    )
    (comp (ref "V201")
      (value "LED-GN/D/0603")
      (footprint "eagle-import:CHIPLED_0603")
      (libsource (lib "eagle-import") (part "led_LEDCHIPLED_0603"))
    )
    (comp (ref "V202")
      (value "LED-R/D/0603")
      (footprint "eagle-import:CHIPLED_0603")
      (libsource (lib "eagle-import") (part "led_LEDCHIPLED_0603"))
    )
    (comp (ref "V203")
      (value "BAT60A")
      (footprint "eagle-import:SOD323-R")
      (libsource (lib "eagle-import") (part "BAT60"))
    )
    (comp (ref "V204")
      (value "ESD8V0L2B-03L")
      (footprint "eagle-import:TSLP-3-1")
      (libsource (lib "eagle-import") (part "ESD8V0L2B-03L"))
    )
  )
  (nets
    (net (code "1") (name "AGND") (class "Default")
      (node (ref "C16") (pin "2") (pinfunction "2_2") (pintype "passive"))
      (node (ref "C17") (pin "2") (pinfunction "2_2") (pintype "passive"))
      (node (ref "XMC4500") (pin "32") (pinfunction "VAGND_32") (pintype "bidirectional"))
      (node (ref "XMC4500") (pin "34") (pinfunction "VSSA_34") (pintype "bidirectional"))
    )
    (net (code "2") (name "AUX_LED#") (class "Default")
      (node (ref "U201") (pin "1") (pinfunction "P0.1_1") (pintype "bidirectional"))
      (node (ref "V202") (pin "C") (pinfunction "C_C") (pintype "passive"))
    )
    (net (code "3") (name "COOLING") (class "Default")
      (node (ref "VREG1") (pin "9") (pinfunction "9_9") (pintype "bidirectional"))
    )
    (net (code "4") (name "CS") (class "Default")
      (node (ref "U201") (pin "23") (pinfunction "P2.3_23") (pintype "bidirectional"))
      (node (ref "U201") (pin "40") (pinfunction "P1.0_40") (pintype "bidirectional"))
    )
    (net (code "5") (name "DBGPRES#") (class "Default")
      (node (ref "C214") (pin "1") (pinfunction "1_1") (pintype "passive"))
      (node (ref "CON2") (pin "9") (pinfunction "9_9") (pintype "passive"))
      (node (ref "R211") (pin "1") (pinfunction "1_1") (pintype "passive"))
      (node (ref "U$9") (pin "P$4") (pinfunction "P$4_P$4") (pintype "bidirectional"))
      (node (ref "U201") (pin "32") (pinfunction "PORST#_32") (pintype "bidirectional"))
    )
    (net (code "6") (name "DEBUG_LED#") (class "Default")
      (node (ref "U201") (pin "48") (pinfunction "P0.2_48") (pintype "bidirectional"))
      (node (ref "V201") (pin "C") (pinfunction "C_C") (pintype "passive"))
    )
    (net (code "7") (name "DEBUG_RX_XMC42{slash}TX_XMC45") (class "Default")
      (node (ref "SJ4") (pin "2") (pinfunction "2_2") (pintype "passive"))
      (node (ref "U201") (pin "46") (pinfunction "P0.4_46") (pintype "bidirectional"))
    )
    (net (code "8") (name "DEBUG_TX_XMC42{slash}RX_XMC45") (class "Default")
      (node (ref "R25") (pin "2") (pinfunction "2_2") (pintype "passive"))
      (node (ref "SJ1") (pin "2") (pinfunction "2_2") (pintype "passive"))
    )
    (net (code "9") (name "GND") (class "Default")
      (node (ref "C1") (pin "2") (pinfunction "2_2") (pintype "passive"))
      (node (ref "C10") (pin "2") (pinfunction "2_2") (pintype "passive"))
      (node (ref "C11") (pin "2") (pinfunction "2_2") (pintype "passive"))
      (node (ref "C12") (pin "2") (pinfunction "2_2") (pintype "passive"))
      (node (ref "C13") (pin "2") (pinfunction "2_2") (pintype "passive"))
      (node (ref "C14") (pin "2") (pinfunction "2_2") (pintype "passive"))
      (node (ref "C15") (pin "1") (pinfunction "1_1") (pintype "passive"))
      (node (ref "C18") (pin "1") (pinfunction "1_1") (pintype "passive"))
      (node (ref "C19") (pin "1") (pinfunction "1_1") (pintype "passive"))
      (node (ref "C2") (pin "2") (pinfunction "2_2") (pintype "passive"))
      (node (ref "C20") (pin "2") (pinfunction "2_2") (pintype "passive"))
      (node (ref "C204") (pin "2") (pinfunction "2_2") (pintype "passive"))
      (node (ref "C205") (pin "2") (pinfunction "2_2") (pintype "passive"))
      (node (ref "C206") (pin "2") (pinfunction "2_2") (pintype "passive"))
      (node (ref "C208") (pin "2") (pinfunction "2_2") (pintype "passive"))
      (node (ref "C209") (pin "2") (pinfunction "2_2") (pintype "passive"))
      (node (ref "C21") (pin "1") (pinfunction "1_1") (pintype "passive"))
      (node (ref "C210") (pin "2") (pinfunction "2_2") (pintype "passive"))
      (node (ref "C211") (pin "2") (pinfunction "2_2") (pintype "passive"))
      (node (ref "C212") (pin "2") (pinfunction "2_2") (pintype "passive"))
      (node (ref "C213") (pin "2") (pinfunction "2_2") (pintype "passive"))
      (node (ref "C214") (pin "2") (pinfunction "2_2") (pintype "passive"))
      (node (ref "C22") (pin "2") (pinfunction "2_2") (pintype "passive"))
      (node (ref "C23") (pin "2") (pinfunction "2_2") (pintype "passive"))
      (node (ref "C24") (pin "1") (pinfunction "1_1") (pintype "passive"))
      (node (ref "C25") (pin "2") (pinfunction "2_2") (pintype "passive"))
      (node (ref "C26") (pin "2") (pinfunction "2_2") (pintype "passive"))
      (node (ref "C27") (pin "2") (pinfunction "2_2") (pintype "passive"))
      (node (ref "C28") (pin "1") (pinfunction "1_1") (pintype "passive"))
      (node (ref "C29") (pin "2") (pinfunction "2_2") (pintype "passive"))
      (node (ref "C3") (pin "2") (pinfunction "2_2") (pintype "passive"))
      (node (ref "C30") (pin "2") (pinfunction "2_2") (pintype "passive"))
      (node (ref "C31") (pin "2") (pinfunction "2_2") (pintype "passive"))
      (node (ref "C32") (pin "2") (pinfunction "2_2") (pintype "passive"))
      (node (ref "C33") (pin "1") (pinfunction "1_1") (pintype "passive"))
      (node (ref "C35") (pin "2") (pinfunction "2_2") (pintype "passive"))
      (node (ref "C37") (pin "2") (pinfunction "2_2") (pintype "passive"))
      (node (ref "C38") (pin "2") (pinfunction "2_2") (pintype "passive"))
      (node (ref "C4") (pin "2") (pinfunction "2_2") (pintype "passive"))
      (node (ref "C5") (pin "2") (pinfunction "2_2") (pintype "passive"))
      (node (ref "C6") (pin "2") (pinfunction "2_2") (pintype "passive"))
      (node (ref "C7") (pin "2") (pinfunction "2_2") (pintype "passive"))
      (node (ref "C8") (pin "2") (pinfunction "2_2") (pintype "passive"))
      (node (ref "C9") (pin "2") (pinfunction "2_2") (pintype "passive"))
      (node (ref "CON10") (pin "1") (pinfunction "1_1") (pintype "passive"))
      (node (ref "CON12") (pin "2") (pinfunction "2_2") (pintype "passive"))
      (node (ref "CON14") (pin "2") (pinfunction "2_2") (pintype "passive"))
      (node (ref "CON15") (pin "2") (pinfunction "2_2") (pintype "passive"))
      (node (ref "CON2") (pin "3") (pinfunction "3_3") (pintype "passive"))
      (node (ref "CON2") (pin "5") (pinfunction "5_5") (pintype "passive"))
      (node (ref "CON3") (pin "1") (pinfunction "1_1") (pintype "passive"))
      (node (ref "CON4") (pin "2") (pinfunction "2_2") (pintype "passive"))
      (node (ref "CON9") (pin "1") (pinfunction "1_1") (pintype "passive"))
      (node (ref "CON9") (pin "3") (pinfunction "3_3") (pintype "passive"))
      (node (ref "D1") (pin "3") (pinfunction "3_3") (pintype "passive"))
      (node (ref "D3") (pin "P$1") (pinfunction "P$1_P$1") (pintype "bidirectional"))
      (node (ref "D4") (pin "P$1") (pinfunction "P$1_P$1") (pintype "bidirectional"))
      (node (ref "D6") (pin "1") (pinfunction "1_1") (pintype "bidirectional"))
      (node (ref "DPS310") (pin "P1") (pinfunction "GND1_P1") (pintype "bidirectional"))
      (node (ref "DPS310") (pin "P7") (pinfunction "GND2_P7") (pintype "bidirectional"))
      (node (ref "IC1") (pin "4") (pinfunction "GND_4") (pintype "bidirectional"))
      (node (ref "IC2") (pin "4") (pinfunction "GND_4") (pintype "bidirectional"))
      (node (ref "LD1") (pin "P_4") (pinfunction "P4/GND_P_4") (pintype "bidirectional"))
      (node (ref "LD2") (pin "P_4") (pinfunction "P4/GND_P_4") (pintype "bidirectional"))
      (node (ref "LD3") (pin "P_4") (pinfunction "P4/GND_P_4") (pintype "bidirectional"))
      (node (ref "LD4") (pin "P_4") (pinfunction "P4/GND_P_4") (pintype "bidirectional"))
      (node (ref "LED1") (pin "C") (pinfunction "C_C") (pintype "passive"))
      (node (ref "LED2") (pin "C") (pinfunction "C_C") (pintype "passive"))
      (node (ref "LED3") (pin "C") (pinfunction "C_C") (pintype "passive"))
      (node (ref "LED4") (pin "C") (pinfunction "C_C") (pintype "passive"))
      (node (ref "LED5") (pin "C") (pinfunction "C_C") (pintype "passive"))
      (node (ref "LED6") (pin "C") (pinfunction "C_C") (pintype "passive"))
      (node (ref "M1_IN") (pin "1") (pinfunction "1_1") (pintype "passive"))
      (node (ref "M1_IN") (pin "2") (pinfunction "2_2") (pintype "passive"))
      (node (ref "M1_OUT") (pin "7") (pinfunction "7_7") (pintype "passive"))
      (node (ref "M1_OUT") (pin "8") (pinfunction "8_8") (pintype "passive"))
      (node (ref "M2_IN") (pin "1") (pinfunction "1_1") (pintype "passive"))
      (node (ref "M2_IN") (pin "2") (pinfunction "2_2") (pintype "passive"))
      (node (ref "M2_OUT") (pin "7") (pinfunction "7_7") (pintype "passive"))
      (node (ref "M2_OUT") (pin "8") (pinfunction "8_8") (pintype "passive"))
      (node (ref "M3_IN") (pin "1") (pinfunction "1_1") (pintype "passive"))
      (node (ref "M3_IN") (pin "2") (pinfunction "2_2") (pintype "passive"))
      (node (ref "M3_OUT") (pin "7") (pinfunction "7_7") (pintype "passive"))
      (node (ref "M3_OUT") (pin "8") (pinfunction "8_8") (pintype "passive"))
      (node (ref "M4_IN") (pin "1") (pinfunction "1_1") (pintype "passive"))
      (node (ref "M4_IN") (pin "2") (pinfunction "2_2") (pintype "passive"))
      (node (ref "M4_OUT") (pin "7") (pinfunction "7_7") (pintype "passive"))
      (node (ref "M4_OUT") (pin "8") (pinfunction "8_8") (pintype "passive"))
      (node (ref "MPU9250") (pin "11") (pinfunction "11_11") (pintype "bidirectional"))
      (node (ref "MPU9250") (pin "18") (pinfunction "18_18") (pintype "bidirectional"))
      (node (ref "MPU9250") (pin "20") (pinfunction "20_20") (pintype "bidirectional"))
      (node (ref "ORIGA") (pin "A1") (pinfunction "A1/VSS_A1") (pintype "bidirectional"))
      (node (ref "ORIGA") (pin "A2") (pinfunction "A2/VSS_A2") (pintype "bidirectional"))
      (node (ref "ORIGA") (pin "C1") (pinfunction "C1/VSS_C1") (pintype "bidirectional"))
      (node (ref "PAD2") (pin "P$1") (pinfunction "P$1_P$1") (pintype "bidirectional"))
      (node (ref "R18") (pin "2") (pinfunction "2_2") (pintype "passive"))
      (node (ref "R19") (pin "2") (pinfunction "2_2") (pintype "passive"))
      (node (ref "R208") (pin "1") (pinfunction "1_1") (pintype "passive"))
      (node (ref "R24") (pin "2") (pinfunction "2_2") (pintype "passive"))
      (node (ref "R26") (pin "2") (pinfunction "2_2") (pintype "passive"))
      (node (ref "R27") (pin "2") (pinfunction "2_2") (pintype "passive"))
      (node (ref "R30") (pin "2") (pinfunction "2_2") (pintype "passive"))
      (node (ref "R32") (pin "2") (pinfunction "2_2") (pintype "passive"))
      (node (ref "R33") (pin "2") (pinfunction "2_2") (pintype "passive"))
      (node (ref "R7") (pin "2") (pinfunction "2_2") (pintype "passive"))
      (node (ref "RN42") (pin "GND1") (pinfunction "1_GND_GND1") (pintype "bidirectional"))
      (node (ref "RN42") (pin "GND2") (pinfunction "12_GND_GND2") (pintype "bidirectional"))
      (node (ref "RN42") (pin "GND3") (pinfunction "29_GND_GND3") (pintype "bidirectional"))
      (node (ref "RN42") (pin "GND4") (pinfunction "28_GND_GND4") (pintype "bidirectional"))
      (node (ref "SW1") (pin "S") (pinfunction "S_S") (pintype "passive"))
      (node (ref "SW1") (pin "S1") (pinfunction "S_S1") (pintype "passive"))
      (node (ref "U$9") (pin "P$5") (pinfunction "P$5_P$5") (pintype "bidirectional"))
      (node (ref "U201") (pin "11") (pinfunction "P14.7_11") (pintype "bidirectional"))
      (node (ref "U201") (pin "12") (pinfunction "P14.6_12") (pintype "bidirectional"))
      (node (ref "U201") (pin "13") (pinfunction "P14.5_13") (pintype "bidirectional"))
      (node (ref "U201") (pin "14") (pinfunction "P14.4_14") (pintype "bidirectional"))
      (node (ref "U201") (pin "17") (pinfunction "VAGND_17") (pintype "bidirectional"))
      (node (ref "U201") (pin "20") (pinfunction "P14.8_20") (pintype "bidirectional"))
      (node (ref "U201") (pin "27") (pinfunction "VSS_27") (pintype "bidirectional"))
      (node (ref "U201") (pin "EPAD") (pinfunction "EPAD_EPAD") (pintype "bidirectional"))
      (node (ref "USB") (pin "1") (pinfunction "1_1") (pintype "passive"))
      (node (ref "USB1") (pin "1") (pinfunction "1_1") (pintype "passive"))
      (node (ref "V204") (pin "3") (pinfunction "3_3") (pintype "passive"))
      (node (ref "VREG1") (pin "1") (pinfunction "1_1") (pintype "bidirectional"))
      (node (ref "VREG1") (pin "2") (pinfunction "2_2") (pintype "bidirectional"))
      (node (ref "VREG2") (pin "1") (pinfunction "ADJ_1") (pintype "power_in"))
      (node (ref "XMC4500") (pin "59") (pinfunction "VSS_59") (pintype "bidirectional"))
      (node (ref "XMC4500") (pin "63") (pinfunction "VSSO_63") (pintype "bidirectional"))
      (node (ref "XMC4500") (pin "EXP") (pinfunction "EPAD_EXP") (pintype "bidirectional"))
    )
    (net (code "10") (name "HIB_IO_0") (class "Default")
      (node (ref "XMC4500") (pin "14") (pinfunction "HIB_IO_0_14") (pintype "bidirectional"))
    )
    (net (code "11") (name "HIB_IO_1") (class "Default")
      (node (ref "XMC4500") (pin "13") (pinfunction "HIB_IO_1_13") (pintype "bidirectional"))
    )
    (net (code "12") (name "LEDOUT1") (class "Default")
      (node (ref "EL1") (pin "2") (pinfunction "2_2") (pintype "passive"))
      (node (ref "LD1") (pin "P_2") (pinfunction "P2/OUT_P_2") (pintype "bidirectional"))
      (node (ref "LD1") (pin "P_3") (pinfunction "P3/OUT_P_3") (pintype "bidirectional"))
      (node (ref "LD1") (pin "P_5") (pinfunction "P5/OUT_P_5") (pintype "bidirectional"))
    )
    (net (code "13") (name "LEDOUT2") (class "Default")
      (node (ref "EL2") (pin "2") (pinfunction "2_2") (pintype "passive"))
      (node (ref "LD2") (pin "P_2") (pinfunction "P2/OUT_P_2") (pintype "bidirectional"))
      (node (ref "LD2") (pin "P_3") (pinfunction "P3/OUT_P_3") (pintype "bidirectional"))
      (node (ref "LD2") (pin "P_5") (pinfunction "P5/OUT_P_5") (pintype "bidirectional"))
    )
    (net (code "14") (name "LEDOUT3") (class "Default")
      (node (ref "EL4") (pin "2") (pinfunction "2_2") (pintype "passive"))
      (node (ref "LD4") (pin "P_2") (pinfunction "P2/OUT_P_2") (pintype "bidirectional"))
      (node (ref "LD4") (pin "P_3") (pinfunction "P3/OUT_P_3") (pintype "bidirectional"))
      (node (ref "LD4") (pin "P_5") (pinfunction "P5/OUT_P_5") (pintype "bidirectional"))
    )
    (net (code "15") (name "LEDOUT4") (class "Default")
      (node (ref "EL3") (pin "2") (pinfunction "2_2") (pintype "passive"))
      (node (ref "LD3") (pin "P_2") (pinfunction "P2/OUT_P_2") (pintype "bidirectional"))
      (node (ref "LD3") (pin "P_3") (pinfunction "P3/OUT_P_3") (pintype "bidirectional"))
      (node (ref "LD3") (pin "P_5") (pinfunction "P5/OUT_P_5") (pintype "bidirectional"))
    )
    (net (code "16") (name "Net-(C19-Pad2)") (class "Default")
      (node (ref "C19") (pin "2") (pinfunction "2_2") (pintype "passive"))
      (node (ref "MPU9250") (pin "10") (pinfunction "10_10") (pintype "bidirectional"))
    )
    (net (code "17") (name "Net-(C34-Pad2)") (class "Default")
      (node (ref "C34") (pin "2") (pinfunction "2_2") (pintype "passive"))
      (node (ref "VREG1") (pin "5") (pinfunction "5_5") (pintype "bidirectional"))
    )
    (net (code "18") (name "Net-(C36-Pad1)") (class "Default")
      (node (ref "C36") (pin "1") (pinfunction "1_1") (pintype "passive"))
      (node (ref "VREG1") (pin "3") (pinfunction "3_3") (pintype "bidirectional"))
    )
    (net (code "19") (name "Net-(C36-Pad2)") (class "Default")
      (node (ref "C36") (pin "2") (pinfunction "2_2") (pintype "passive"))
      (node (ref "R24") (pin "1") (pinfunction "1_1") (pintype "passive"))
    )
    (net (code "20") (name "Net-(C205-Pad1)") (class "Default")
      (node (ref "C205") (pin "1") (pinfunction "1_1") (pintype "passive"))
      (node (ref "Q2") (pin "1") (pinfunction "1_1") (pintype "passive"))
      (node (ref "R205") (pin "2") (pinfunction "2_2") (pintype "passive"))
    )
    (net (code "21") (name "Net-(CON5-Pad1)") (class "Default")
      (node (ref "CON5") (pin "1") (pinfunction "1_1") (pintype "passive"))
      (node (ref "M1_OUT") (pin "5") (pinfunction "5_5") (pintype "passive"))
      (node (ref "M1_OUT") (pin "6") (pinfunction "6_6") (pintype "passive"))
    )
    (net (code "22") (name "Net-(CON5-Pad2)") (class "Default")
      (node (ref "CON5") (pin "2") (pinfunction "2_2") (pintype "passive"))
      (node (ref "M1_OUT") (pin "3") (pinfunction "3_3") (pintype "passive"))
      (node (ref "M1_OUT") (pin "4") (pinfunction "4_4") (pintype "passive"))
    )
    (net (code "23") (name "Net-(CON5-Pad3)") (class "Default")
      (node (ref "CON5") (pin "3") (pinfunction "3_3") (pintype "passive"))
      (node (ref "M1_OUT") (pin "1") (pinfunction "1_1") (pintype "passive"))
      (node (ref "M1_OUT") (pin "2") (pinfunction "2_2") (pintype "passive"))
    )
    (net (code "24") (name "Net-(CON6-Pad1)") (class "Default")
      (node (ref "CON6") (pin "1") (pinfunction "1_1") (pintype "passive"))
      (node (ref "M2_OUT") (pin "5") (pinfunction "5_5") (pintype "passive"))
      (node (ref "M2_OUT") (pin "6") (pinfunction "6_6") (pintype "passive"))
    )
    (net (code "25") (name "Net-(CON6-Pad2)") (class "Default")
      (node (ref "CON6") (pin "2") (pinfunction "2_2") (pintype "passive"))
      (node (ref "M2_OUT") (pin "3") (pinfunction "3_3") (pintype "passive"))
      (node (ref "M2_OUT") (pin "4") (pinfunction "4_4") (pintype "passive"))
    )
    (net (code "26") (name "Net-(CON6-Pad3)") (class "Default")
      (node (ref "CON6") (pin "3") (pinfunction "3_3") (pintype "passive"))
      (node (ref "M2_OUT") (pin "1") (pinfunction "1_1") (pintype "passive"))
      (node (ref "M2_OUT") (pin "2") (pinfunction "2_2") (pintype "passive"))
    )
    (net (code "27") (name "Net-(CON7-Pad1)") (class "Default")
      (node (ref "CON7") (pin "1") (pinfunction "1_1") (pintype "passive"))
      (node (ref "M3_OUT") (pin "5") (pinfunction "5_5") (pintype "passive"))
      (node (ref "M3_OUT") (pin "6") (pinfunction "6_6") (pintype "passive"))
    )
    (net (code "28") (name "Net-(CON7-Pad2)") (class "Default")
      (node (ref "CON7") (pin "2") (pinfunction "2_2") (pintype "passive"))
      (node (ref "M3_OUT") (pin "3") (pinfunction "3_3") (pintype "passive"))
      (node (ref "M3_OUT") (pin "4") (pinfunction "4_4") (pintype "passive"))
    )
    (net (code "29") (name "Net-(CON7-Pad3)") (class "Default")
      (node (ref "CON7") (pin "3") (pinfunction "3_3") (pintype "passive"))
      (node (ref "M3_OUT") (pin "1") (pinfunction "1_1") (pintype "passive"))
      (node (ref "M3_OUT") (pin "2") (pinfunction "2_2") (pintype "passive"))
    )
    (net (code "30") (name "Net-(CON8-Pad1)") (class "Default")
      (node (ref "CON8") (pin "1") (pinfunction "1_1") (pintype "passive"))
      (node (ref "M4_OUT") (pin "5") (pinfunction "5_5") (pintype "passive"))
      (node (ref "M4_OUT") (pin "6") (pinfunction "6_6") (pintype "passive"))
    )
    (net (code "31") (name "Net-(CON8-Pad2)") (class "Default")
      (node (ref "CON8") (pin "2") (pinfunction "2_2") (pintype "passive"))
      (node (ref "M4_OUT") (pin "3") (pinfunction "3_3") (pintype "passive"))
      (node (ref "M4_OUT") (pin "4") (pinfunction "4_4") (pintype "passive"))
    )
    (net (code "32") (name "Net-(CON8-Pad3)") (class "Default")
      (node (ref "CON8") (pin "3") (pinfunction "3_3") (pintype "passive"))
      (node (ref "M4_OUT") (pin "1") (pinfunction "1_1") (pintype "passive"))
      (node (ref "M4_OUT") (pin "2") (pinfunction "2_2") (pintype "passive"))
    )
    (net (code "33") (name "Net-(CON11-Pad1)") (class "Default")
      (node (ref "CON11") (pin "1") (pinfunction "1_1") (pintype "passive"))
      (node (ref "R13") (pin "1") (pinfunction "1_1") (pintype "passive"))
    )
    (net (code "34") (name "Net-(CON11-Pad2)") (class "Default")
      (node (ref "CON11") (pin "2") (pinfunction "2_2") (pintype "passive"))
      (node (ref "R28") (pin "1") (pinfunction "1_1") (pintype "passive"))
    )
    (net (code "35") (name "Net-(CON11-Pad3)") (class "Default")
      (node (ref "CON11") (pin "3") (pinfunction "3_3") (pintype "passive"))
      (node (ref "R29") (pin "1") (pinfunction "1_1") (pintype "passive"))
    )
    (net (code "36") (name "Net-(D1-Pad2)") (class "Default")
      (node (ref "D1") (pin "2") (pinfunction "2_2") (pintype "passive"))
      (node (ref "R10") (pin "1") (pinfunction "1_1") (pintype "passive"))
      (node (ref "USB") (pin "4") (pinfunction "4_4") (pintype "passive"))
    )
    (net (code "37") (name "Net-(D4-PadP$2)") (class "Default")
      (node (ref "D4") (pin "P$2") (pinfunction "P$2_P$2") (pintype "bidirectional"))
      (node (ref "JP1") (pin "1") (pinfunction "1_1") (pintype "passive"))
      (node (ref "R3") (pin "2") (pinfunction "2_2") (pintype "passive"))
      (node (ref "R4") (pin "2") (pinfunction "2_2") (pintype "passive"))
      (node (ref "R7") (pin "1") (pinfunction "1_1") (pintype "passive"))
    )
    (net (code "38") (name "Net-(D5-C)") (class "Default")
      (node (ref "CON2") (pin "10") (pinfunction "10_10") (pintype "passive"))
      (node (ref "D5") (pin "1") (pinfunction "C_1") (pintype "passive"))
    )
    (net (code "39") (name "Net-(L1-Pad2)") (class "Default")
      (node (ref "L1") (pin "2") (pinfunction "2_2") (pintype "passive"))
      (node (ref "USB") (pin "5") (pinfunction "5_5") (pintype "passive"))
    )
    (net (code "40") (name "Net-(L4-1)") (class "Default")
      (node (ref "C24") (pin "2") (pinfunction "2_2") (pintype "passive"))
      (node (ref "L4") (pin "P$1") (pinfunction "1_P$1") (pintype "bidirectional"))
      (node (ref "VREG1") (pin "8") (pinfunction "8_8") (pintype "bidirectional"))
    )
    (net (code "41") (name "Net-(L5-1)") (class "Default")
      (node (ref "C34") (pin "1") (pinfunction "1_1") (pintype "passive"))
      (node (ref "D6") (pin "2") (pinfunction "2_2") (pintype "bidirectional"))
      (node (ref "L5") (pin "P$1") (pinfunction "1_P$1") (pintype "bidirectional"))
      (node (ref "VREG1") (pin "6") (pinfunction "6_6") (pintype "bidirectional"))
    )
    (net (code "42") (name "Net-(L6-Pad1)") (class "Default")
      (node (ref "L6") (pin "1") (pinfunction "1_1") (pintype "passive"))
      (node (ref "USB1") (pin "5") (pinfunction "5_5") (pintype "passive"))
    )
    (net (code "43") (name "Net-(L6-Pad2)") (class "Default")
      (node (ref "L6") (pin "2") (pinfunction "2_2") (pintype "passive"))
      (node (ref "R207") (pin "2") (pinfunction "2_2") (pintype "passive"))
      (node (ref "V203") (pin "A") (pinfunction "A_A") (pintype "passive"))
    )
    (net (code "44") (name "Net-(LD1-P6{slash}REXT)") (class "Default")
      (node (ref "LD1") (pin "P_6") (pinfunction "P6/REXT_P_6") (pintype "bidirectional"))
      (node (ref "R27") (pin "1") (pinfunction "1_1") (pintype "passive"))
    )
    (net (code "45") (name "Net-(LD2-P6{slash}REXT)") (class "Default")
      (node (ref "LD2") (pin "P_6") (pinfunction "P6/REXT_P_6") (pintype "bidirectional"))
      (node (ref "R26") (pin "1") (pinfunction "1_1") (pintype "passive"))
    )
    (net (code "46") (name "Net-(LD3-P6{slash}REXT)") (class "Default")
      (node (ref "LD3") (pin "P_6") (pinfunction "P6/REXT_P_6") (pintype "bidirectional"))
      (node (ref "R32") (pin "1") (pinfunction "1_1") (pintype "passive"))
    )
    (net (code "47") (name "Net-(LD4-P6{slash}REXT)") (class "Default")
      (node (ref "LD4") (pin "P_6") (pinfunction "P6/REXT_P_6") (pintype "bidirectional"))
      (node (ref "R33") (pin "1") (pinfunction "1_1") (pintype "passive"))
    )
    (net (code "48") (name "Net-(LED1-PadA)") (class "Default")
      (node (ref "LED1") (pin "A") (pinfunction "A_A") (pintype "passive"))
      (node (ref "R6") (pin "1") (pinfunction "1_1") (pintype "passive"))
    )
    (net (code "49") (name "Net-(LED2-PadA)") (class "Default")
      (node (ref "LED2") (pin "A") (pinfunction "A_A") (pintype "passive"))
      (node (ref "R20") (pin "1") (pinfunction "1_1") (pintype "passive"))
    )
    (net (code "50") (name "Net-(LED3-PadA)") (class "Default")
      (node (ref "LED3") (pin "A") (pinfunction "A_A") (pintype "passive"))
      (node (ref "R21") (pin "1") (pinfunction "1_1") (pintype "passive"))
    )
    (net (code "51") (name "Net-(LED4-PadA)") (class "Default")
      (node (ref "LED4") (pin "A") (pinfunction "A_A") (pintype "passive"))
      (node (ref "R22") (pin "1") (pinfunction "1_1") (pintype "passive"))
    )
    (net (code "52") (name "Net-(LED5-PadA)") (class "Default")
      (node (ref "LED5") (pin "A") (pinfunction "A_A") (pintype "passive"))
      (node (ref "R23") (pin "1") (pinfunction "1_1") (pintype "passive"))
    )
    (net (code "53") (name "Net-(LED6-PadA)") (class "Default")
      (node (ref "LED6") (pin "A") (pinfunction "A_A") (pintype "passive"))
      (node (ref "R5") (pin "1") (pinfunction "1_1") (pintype "passive"))
    )
    (net (code "54") (name "Net-(M1_IN-Pad6)") (class "Default")
      (node (ref "M1_IN") (pin "6") (pinfunction "6_6") (pintype "passive"))
      (node (ref "M2_IN") (pin "5") (pinfunction "5_5") (pintype "passive"))
      (node (ref "R35") (pin "1") (pinfunction "1_1") (pintype "passive"))
    )
    (net (code "55") (name "Net-(M2_IN-Pad6)") (class "Default")
      (node (ref "M2_IN") (pin "6") (pinfunction "6_6") (pintype "passive"))
      (node (ref "M3_IN") (pin "5") (pinfunction "5_5") (pintype "passive"))
      (node (ref "R37") (pin "1") (pinfunction "1_1") (pintype "passive"))
    )
    (net (code "56") (name "Net-(M3_IN-Pad6)") (class "Default")
      (node (ref "M3_IN") (pin "6") (pinfunction "6_6") (pintype "passive"))
      (node (ref "M4_IN") (pin "5") (pinfunction "5_5") (pintype "passive"))
      (node (ref "R38") (pin "1") (pinfunction "1_1") (pintype "passive"))
    )
    (net (code "57") (name "Net-(ORIGA-B2{slash}VDD)") (class "Default")
      (node (ref "C28") (pin "2") (pinfunction "2_2") (pintype "passive"))
      (node (ref "ORIGA") (pin "B2") (pinfunction "B2/VDD_B2") (pintype "bidirectional"))
      (node (ref "R2") (pin "2") (pinfunction "2_2") (pintype "passive"))
    )
    (net (code "58") (name "Net-(ORIGA-C2{slash}BIF)") (class "Default")
      (node (ref "ORIGA") (pin "C2") (pinfunction "C2/BIF_C2") (pintype "bidirectional"))
      (node (ref "R3") (pin "1") (pinfunction "1_1") (pintype "passive"))
    )
    (net (code "59") (name "Net-(Q1-2)") (class "Default")
      (node (ref "C13") (pin "1") (pinfunction "1_1") (pintype "passive"))
      (node (ref "Q1") (pin "3") (pinfunction "2_3") (pintype "passive"))
      (node (ref "R12") (pin "2") (pinfunction "2_2") (pintype "passive"))
    )
    (net (code "60") (name "Net-(Q2-2)") (class "Default")
      (node (ref "C206") (pin "1") (pinfunction "1_1") (pintype "passive"))
      (node (ref "Q2") (pin "3") (pinfunction "2_3") (pintype "passive"))
      (node (ref "U201") (pin "29") (pinfunction "XTAL1_29") (pintype "bidirectional"))
    )
    (net (code "61") (name "Net-(R201-Pad2)") (class "Default")
      (node (ref "R201") (pin "2") (pinfunction "2_2") (pintype "passive"))
      (node (ref "V201") (pin "A") (pinfunction "A_A") (pintype "passive"))
    )
    (net (code "62") (name "Net-(R202-Pad2)") (class "Default")
      (node (ref "R202") (pin "2") (pinfunction "2_2") (pintype "passive"))
      (node (ref "V202") (pin "A") (pinfunction "A_A") (pintype "passive"))
    )
    (net (code "63") (name "Net-(R204-Pad2)") (class "Default")
      (node (ref "R204") (pin "2") (pinfunction "2_2") (pintype "passive"))
      (node (ref "USB1") (pin "4") (pinfunction "4_4") (pintype "passive"))
      (node (ref "V204") (pin "1") (pinfunction "1_1") (pintype "passive"))
    )
    (net (code "64") (name "Net-(RN42-13_RX)") (class "Default")
      (node (ref "CON10") (pin "4") (pinfunction "4_4") (pintype "passive"))
      (node (ref "RN42") (pin "UART_RX") (pinfunction "13_RX_UART_RX") (pintype "bidirectional"))
      (node (ref "SJ3") (pin "2") (pinfunction "2_2") (pintype "passive"))
    )
    (net (code "65") (name "Net-(RN42-14_TX)") (class "Default")
      (node (ref "CON10") (pin "2") (pinfunction "2_2") (pintype "passive"))
      (node (ref "RN42") (pin "UART_TX") (pinfunction "14_TX_UART_TX") (pintype "bidirectional"))
      (node (ref "SJ2") (pin "2") (pinfunction "2_2") (pintype "passive"))
    )
    (net (code "66") (name "Net-(RN42-15_RTS)") (class "Default")
      (node (ref "RN42") (pin "UART_CTX") (pinfunction "16_CTS_UART_CTX") (pintype "bidirectional"))
      (node (ref "RN42") (pin "UART_RTX") (pinfunction "15_RTS_UART_RTX") (pintype "bidirectional"))
    )
    (net (code "67") (name "Net-(RN42-19_LED)") (class "Default")
      (node (ref "R6") (pin "2") (pinfunction "2_2") (pintype "passive"))
      (node (ref "RN42") (pin "GPIO_2") (pinfunction "19_LED_GPIO_2") (pintype "bidirectional"))
    )
    (net (code "68") (name "Net-(U201-HIB_IO_0)") (class "Default")
      (node (ref "R207") (pin "1") (pinfunction "1_1") (pintype "passive"))
      (node (ref "R208") (pin "2") (pinfunction "2_2") (pintype "passive"))
      (node (ref "U201") (pin "7") (pinfunction "HIB_IO_0_7") (pintype "bidirectional"))
    )
    (net (code "69") (name "Net-(U201-P0.5)") (class "Default")
      (node (ref "R25") (pin "1") (pinfunction "1_1") (pintype "passive"))
      (node (ref "U201") (pin "45") (pinfunction "P0.5_45") (pintype "bidirectional"))
    )
    (net (code "70") (name "Net-(U201-USB_D+)") (class "Default")
      (node (ref "R206") (pin "1") (pinfunction "1_1") (pintype "passive"))
      (node (ref "U201") (pin "4") (pinfunction "USB_D+_4") (pintype "bidirectional"))
    )
    (net (code "71") (name "Net-(U201-USB_D-)") (class "Default")
      (node (ref "R204") (pin "1") (pinfunction "1_1") (pintype "passive"))
      (node (ref "U201") (pin "3") (pinfunction "USB_D-_3") (pintype "bidirectional"))
    )
    (net (code "72") (name "Net-(U201-VDDC)") (class "Default")
      (node (ref "C208") (pin "1") (pinfunction "1_1") (pintype "passive"))
      (node (ref "C209") (pin "1") (pinfunction "1_1") (pintype "passive"))
      (node (ref "C210") (pin "1") (pinfunction "1_1") (pintype "passive"))
      (node (ref "U201") (pin "31") (pinfunction "VDDC1_31") (pintype "bidirectional"))
      (node (ref "U201") (pin "6") (pinfunction "VDDC_6") (pintype "bidirectional"))
    )
    (net (code "73") (name "Net-(U201-XTAL2)") (class "Default")
      (node (ref "R205") (pin "1") (pinfunction "1_1") (pintype "passive"))
      (node (ref "U201") (pin "30") (pinfunction "XTAL2_30") (pintype "bidirectional"))
    )
    (net (code "74") (name "Net-(USB-3)") (class "Default")
      (node (ref "D1") (pin "1") (pinfunction "1_1") (pintype "passive"))
      (node (ref "R11") (pin "1") (pinfunction "1_1") (pintype "passive"))
      (node (ref "USB") (pin "3+") (pinfunction "3_3+") (pintype "passive"))
    )
    (net (code "75") (name "Net-(USB1-3)") (class "Default")
      (node (ref "R206") (pin "2") (pinfunction "2_2") (pintype "passive"))
      (node (ref "USB1") (pin "3+") (pinfunction "3_3+") (pintype "passive"))
      (node (ref "V204") (pin "2") (pinfunction "2_2") (pintype "passive"))
    )
    (net (code "76") (name "Net-(XMC4500-XTAL1)") (class "Default")
      (node (ref "C12") (pin "1") (pinfunction "1_1") (pintype "passive"))
      (node (ref "Q1") (pin "1") (pinfunction "1_1") (pintype "passive"))
      (node (ref "XMC4500") (pin "61") (pinfunction "XTAL1_61") (pintype "bidirectional"))
    )
    (net (code "77") (name "Net-(XMC4500-XTAL2)") (class "Default")
      (node (ref "R12") (pin "1") (pinfunction "1_1") (pintype "passive"))
      (node (ref "XMC4500") (pin "62") (pinfunction "XTAL2_62") (pintype "bidirectional"))
    )
    (net (code "78") (name "P0.0") (class "Default")
      (node (ref "M4_IN") (pin "6") (pinfunction "6_6") (pintype "passive"))
      (node (ref "SJ4") (pin "1") (pinfunction "1_1") (pintype "passive"))
      (node (ref "XMC4500") (pin "2") (pinfunction "P0.0_2") (pintype "bidirectional"))
    )
    (net (code "79") (name "P0.1") (class "Default")
      (node (ref "M1_IN") (pin "5") (pinfunction "5_5") (pintype "passive"))
      (node (ref "R36") (pin "1") (pinfunction "1_1") (pintype "passive"))
      (node (ref "SJ1") (pin "1") (pinfunction "1_1") (pintype "passive"))
      (node (ref "XMC4500") (pin "1") (pinfunction "P0.1_1") (pintype "bidirectional"))
    )
    (net (code "80") (name "P0.2") (class "Default")
      (node (ref "LD1") (pin "P_1") (pinfunction "P1/EN_P_1") (pintype "bidirectional"))
      (node (ref "XMC4500") (pin "100") (pinfunction "P0.2_100") (pintype "bidirectional"))
    )
    (net (code "81") (name "P0.3") (class "Default")
      (node (ref "LD2") (pin "P_1") (pinfunction "P1/EN_P_1") (pintype "bidirectional"))
      (node (ref "XMC4500") (pin "99") (pinfunction "P0.3_99") (pintype "bidirectional"))
    )
    (net (code "82") (name "P0.4") (class "Default")
      (node (ref "CON4") (pin "3") (pinfunction "3_3") (pintype "passive"))
      (node (ref "XMC4500") (pin "98") (pinfunction "P0.4_98") (pintype "bidirectional"))
    )
    (net (code "83") (name "P0.5") (class "Default")
      (node (ref "CON15") (pin "8") (pinfunction "8_8") (pintype "passive"))
      (node (ref "MPU9250") (pin "12") (pinfunction "12_12") (pintype "bidirectional"))
      (node (ref "XMC4500") (pin "97") (pinfunction "P0.5_97") (pintype "bidirectional"))
    )
    (net (code "84") (name "P0.6") (class "Default")
      (node (ref "XMC4500") (pin "96") (pinfunction "P0.6_96") (pintype "bidirectional"))
    )
    (net (code "85") (name "P0.7") (class "Default")
      (node (ref "CON2") (pin "8") (pinfunction "8_8") (pintype "passive"))
      (node (ref "XMC4500") (pin "89") (pinfunction "P0.7_89") (pintype "bidirectional"))
    )
    (net (code "86") (name "P0.8") (class "Default")
      (node (ref "XMC4500") (pin "88") (pinfunction "P0.8_88") (pintype "bidirectional"))
    )
    (net (code "87") (name "P0.9") (class "Default")
      (node (ref "R20") (pin "2") (pinfunction "2_2") (pintype "passive"))
      (node (ref "XMC4500") (pin "4") (pinfunction "P0.9_4") (pintype "bidirectional"))
    )
    (net (code "88") (name "P0.10") (class "Default")
      (node (ref "JP1") (pin "2") (pinfunction "2_2") (pintype "passive"))
      (node (ref "XMC4500") (pin "3") (pinfunction "P0.10_3") (pintype "bidirectional"))
    )
    (net (code "89") (name "P0.11") (class "Default")
      (node (ref "XMC4500") (pin "95") (pinfunction "P0.11_95") (pintype "bidirectional"))
    )
    (net (code "90") (name "P0.12") (class "Default")
      (node (ref "XMC4500") (pin "94") (pinfunction "P0.12_94") (pintype "bidirectional"))
    )
    (net (code "91") (name "P1.0") (class "Default")
      (node (ref "IC1") (pin "2") (pinfunction "A1_2") (pintype "bidirectional"))
      (node (ref "XMC4500") (pin "79") (pinfunction "P1.0_79") (pintype "bidirectional"))
    )
    (net (code "92") (name "P1.1") (class "Default")
      (node (ref "IC1") (pin "3") (pinfunction "A2_3") (pintype "bidirectional"))
      (node (ref "XMC4500") (pin "78") (pinfunction "P1.1_78") (pintype "bidirectional"))
    )
    (net (code "93") (name "P1.2") (class "Default")
      (node (ref "IC2") (pin "2") (pinfunction "A1_2") (pintype "bidirectional"))
      (node (ref "XMC4500") (pin "77") (pinfunction "P1.2_77") (pintype "bidirectional"))
    )
    (net (code "94") (name "P1.3") (class "Default")
      (node (ref "IC2") (pin "3") (pinfunction "A2_3") (pintype "bidirectional"))
      (node (ref "XMC4500") (pin "76") (pinfunction "P1.3_76") (pintype "bidirectional"))
    )
    (net (code "95") (name "P1.4") (class "Default")
      (node (ref "XMC4500") (pin "75") (pinfunction "P1.4_75") (pintype "bidirectional"))
    )
    (net (code "96") (name "P1.5") (class "Default")
      (node (ref "R8") (pin "2") (pinfunction "2_2") (pintype "passive"))
      (node (ref "SJ2") (pin "1") (pinfunction "1_1") (pintype "passive"))
      (node (ref "XMC4500") (pin "74") (pinfunction "P1.5_74") (pintype "bidirectional"))
    )
    (net (code "97") (name "P1.6") (class "Default")
      (node (ref "XMC4500") (pin "83") (pinfunction "P1.6_83") (pintype "bidirectional"))
    )
    (net (code "98") (name "P1.7") (class "Default")
      (node (ref "XMC4500") (pin "82") (pinfunction "P1.7_82") (pintype "bidirectional"))
    )
    (net (code "99") (name "P1.8") (class "Default")
      (node (ref "XMC4500") (pin "81") (pinfunction "P1.8_81") (pintype "bidirectional"))
    )
    (net (code "100") (name "P1.9") (class "Default")
      (node (ref "XMC4500") (pin "80") (pinfunction "P1.9_80") (pintype "bidirectional"))
    )
    (net (code "101") (name "P1.10") (class "Default")
      (node (ref "XMC4500") (pin "73") (pinfunction "P1.10_73") (pintype "bidirectional"))
    )
    (net (code "102") (name "P1.11") (class "Default")
      (node (ref "XMC4500") (pin "72") (pinfunction "P1.11_72") (pintype "bidirectional"))
    )
    (net (code "103") (name "P1.12") (class "Default")
      (node (ref "XMC4500") (pin "71") (pinfunction "P1.12_71") (pintype "bidirectional"))
    )
    (net (code "104") (name "P1.13") (class "Default")
      (node (ref "XMC4500") (pin "70") (pinfunction "P1.13_70") (pintype "bidirectional"))
    )
    (net (code "105") (name "P1.14") (class "Default")
      (node (ref "XMC4500") (pin "69") (pinfunction "P1.14_69") (pintype "bidirectional"))
    )
    (net (code "106") (name "P1.15") (class "Default")
      (node (ref "CON13") (pin "3") (pinfunction "3_3") (pintype "passive"))
      (node (ref "DPS310") (pin "P5") (pinfunction "SDO_P5") (pintype "bidirectional"))
      (node (ref "XMC4500") (pin "68") (pinfunction "P1.15_68") (pintype "bidirectional"))
    )
    (net (code "107") (name "P2.0") (class "Default")
      (node (ref "XMC4500") (pin "52") (pinfunction "P2.0_52") (pintype "bidirectional"))
    )
    (net (code "108") (name "P2.1") (class "Default")
      (node (ref "CON2") (pin "6") (pinfunction "6_6") (pintype "passive"))
      (node (ref "XMC4500") (pin "51") (pinfunction "P2.1_51") (pintype "bidirectional"))
    )
    (net (code "109") (name "P2.2") (class "Default")
      (node (ref "LD4") (pin "P_1") (pinfunction "P1/EN_P_1") (pintype "bidirectional"))
      (node (ref "XMC4500") (pin "50") (pinfunction "P2.2_50") (pintype "bidirectional"))
    )
    (net (code "110") (name "P2.3") (class "Default")
      (node (ref "LD3") (pin "P_1") (pinfunction "P1/EN_P_1") (pintype "bidirectional"))
      (node (ref "XMC4500") (pin "49") (pinfunction "P2.3_49") (pintype "bidirectional"))
    )
    (net (code "111") (name "P2.4") (class "Default")
      (node (ref "CON13") (pin "2") (pinfunction "2_2") (pintype "passive"))
      (node (ref "DPS310") (pin "P4") (pinfunction "SCK_P4") (pintype "bidirectional"))
      (node (ref "R16") (pin "2") (pinfunction "2_2") (pintype "passive"))
      (node (ref "XMC4500") (pin "48") (pinfunction "P2.4_48") (pintype "bidirectional"))
    )
    (net (code "112") (name "P2.5") (class "Default")
      (node (ref "CON13") (pin "1") (pinfunction "1_1") (pintype "passive"))
      (node (ref "DPS310") (pin "P3") (pinfunction "SDI_P3") (pintype "bidirectional"))
      (node (ref "R17") (pin "2") (pinfunction "2_2") (pintype "passive"))
      (node (ref "XMC4500") (pin "47") (pinfunction "P2.5_47") (pintype "bidirectional"))
    )
    (net (code "113") (name "P2.6") (class "Default")
      (node (ref "XMC4500") (pin "54") (pinfunction "P2.6_54") (pintype "bidirectional"))
    )
    (net (code "114") (name "P2.7") (class "Default")
      (node (ref "XMC4500") (pin "53") (pinfunction "P2.7_53") (pintype "bidirectional"))
    )
    (net (code "115") (name "P2.8") (class "Default")
      (node (ref "XMC4500") (pin "46") (pinfunction "P2.8_46") (pintype "bidirectional"))
    )
    (net (code "116") (name "P2.9") (class "Default")
      (node (ref "XMC4500") (pin "45") (pinfunction "P2.9_45") (pintype "bidirectional"))
    )
    (net (code "117") (name "P2.10") (class "Default")
      (node (ref "XMC4500") (pin "44") (pinfunction "P2.10_44") (pintype "bidirectional"))
    )
    (net (code "118") (name "P2.14") (class "Default")
      (node (ref "XMC4500") (pin "41") (pinfunction "P2.14_41") (pintype "bidirectional"))
    )
    (net (code "119") (name "P2.15") (class "Default")
      (node (ref "XMC4500") (pin "40") (pinfunction "P2.15_40") (pintype "bidirectional"))
    )
    (net (code "120") (name "P3.0") (class "Default")
      (node (ref "R22") (pin "2") (pinfunction "2_2") (pintype "passive"))
      (node (ref "XMC4500") (pin "7") (pinfunction "P3.0_7") (pintype "bidirectional"))
    )
    (net (code "121") (name "P3.1") (class "Default")
      (node (ref "R23") (pin "2") (pinfunction "2_2") (pintype "passive"))
      (node (ref "XMC4500") (pin "6") (pinfunction "P3.1_6") (pintype "bidirectional"))
    )
    (net (code "122") (name "P3.2") (class "Default")
      (node (ref "R21") (pin "2") (pinfunction "2_2") (pintype "passive"))
      (node (ref "XMC4500") (pin "5") (pinfunction "P3.2_5") (pintype "bidirectional"))
    )
    (net (code "123") (name "P3.3") (class "Default")
      (node (ref "XMC4500") (pin "93") (pinfunction "P3.3_93") (pintype "bidirectional"))
    )
    (net (code "124") (name "P3.4") (class "Default")
      (node (ref "XMC4500") (pin "92") (pinfunction "P3.4_92") (pintype "bidirectional"))
    )
    (net (code "125") (name "P3.5") (class "Default")
      (node (ref "CON3") (pin "3") (pinfunction "3_3") (pintype "passive"))
      (node (ref "XMC4500") (pin "91") (pinfunction "P3.5_91") (pintype "bidirectional"))
    )
    (net (code "126") (name "P3.6") (class "Default")
      (node (ref "XMC4500") (pin "90") (pinfunction "P3.6_90") (pintype "bidirectional"))
    )
    (net (code "127") (name "P4.0") (class "Default")
      (node (ref "CON3") (pin "4") (pinfunction "4_4") (pintype "passive"))
      (node (ref "XMC4500") (pin "85") (pinfunction "P4.0_85") (pintype "bidirectional"))
    )
    (net (code "128") (name "P4.1") (class "Default")
      (node (ref "XMC4500") (pin "84") (pinfunction "P4.1_84") (pintype "bidirectional"))
    )
    (net (code "129") (name "P5.0") (class "Default")
      (node (ref "CON15") (pin "4") (pinfunction "4_4") (pintype "passive"))
      (node (ref "MPU9250") (pin "24") (pinfunction "24_24") (pintype "bidirectional"))
      (node (ref "R15") (pin "1") (pinfunction "1_1") (pintype "passive"))
      (node (ref "XMC4500") (pin "58") (pinfunction "P5.0_58") (pintype "bidirectional"))
    )
    (net (code "130") (name "P5.1") (class "Default")
      (node (ref "R9") (pin "2") (pinfunction "2_2") (pintype "passive"))
      (node (ref "SJ3") (pin "1") (pinfunction "1_1") (pintype "passive"))
      (node (ref "XMC4500") (pin "57") (pinfunction "P5.1_57") (pintype "bidirectional"))
    )
    (net (code "131") (name "P5.2") (class "Default")
      (node (ref "CON15") (pin "3") (pinfunction "3_3") (pintype "passive"))
      (node (ref "MPU9250") (pin "23") (pinfunction "23_23") (pintype "bidirectional"))
      (node (ref "R14") (pin "1") (pinfunction "1_1") (pintype "passive"))
      (node (ref "XMC4500") (pin "56") (pinfunction "P5.2_56") (pintype "bidirectional"))
    )
    (net (code "132") (name "P5.7") (class "Default")
      (node (ref "XMC4500") (pin "55") (pinfunction "P5.7_55") (pintype "bidirectional"))
    )
    (net (code "133") (name "P14.0") (class "Default")
      (node (ref "XMC4500") (pin "31") (pinfunction "P14.0_31") (pintype "bidirectional"))
    )
    (net (code "134") (name "P14.1") (class "Default")
      (node (ref "XMC4500") (pin "30") (pinfunction "P14.1_30") (pintype "bidirectional"))
    )
    (net (code "135") (name "P14.2") (class "Default")
      (node (ref "XMC4500") (pin "29") (pinfunction "P14.2_29") (pintype "bidirectional"))
    )
    (net (code "136") (name "P14.3") (class "Default")
      (node (ref "XMC4500") (pin "28") (pinfunction "P14.3_28") (pintype "bidirectional"))
    )
    (net (code "137") (name "P14.4") (class "Default")
      (node (ref "XMC4500") (pin "27") (pinfunction "P14.4_27") (pintype "bidirectional"))
    )
    (net (code "138") (name "P14.5") (class "Default")
      (node (ref "C29") (pin "1") (pinfunction "1_1") (pintype "passive"))
      (node (ref "R13") (pin "2") (pinfunction "2_2") (pintype "passive"))
      (node (ref "R18") (pin "1") (pinfunction "1_1") (pintype "passive"))
      (node (ref "XMC4500") (pin "26") (pinfunction "P14.5_26") (pintype "bidirectional"))
    )
    (net (code "139") (name "P14.6") (class "Default")
      (node (ref "XMC4500") (pin "25") (pinfunction "P14.6_25") (pintype "bidirectional"))
    )
    (net (code "140") (name "P14.7") (class "Default")
      (node (ref "C31") (pin "1") (pinfunction "1_1") (pintype "passive"))
      (node (ref "R29") (pin "2") (pinfunction "2_2") (pintype "passive"))
      (node (ref "R30") (pin "1") (pinfunction "1_1") (pintype "passive"))
      (node (ref "XMC4500") (pin "24") (pinfunction "P14.7_24") (pintype "bidirectional"))
    )
    (net (code "141") (name "P14.8") (class "Default")
      (node (ref "C30") (pin "1") (pinfunction "1_1") (pintype "passive"))
      (node (ref "R19") (pin "1") (pinfunction "1_1") (pintype "passive"))
      (node (ref "R28") (pin "2") (pinfunction "2_2") (pintype "passive"))
      (node (ref "XMC4500") (pin "37") (pinfunction "P14.8_37") (pintype "bidirectional"))
    )
    (net (code "142") (name "P14.9") (class "Default")
      (node (ref "XMC4500") (pin "36") (pinfunction "P14.9_36") (pintype "bidirectional"))
    )
    (net (code "143") (name "P14.12") (class "Default")
      (node (ref "XMC4500") (pin "23") (pinfunction "P14.12_23") (pintype "bidirectional"))
    )
    (net (code "144") (name "P14.13") (class "Default")
      (node (ref "XMC4500") (pin "22") (pinfunction "P14.13_22") (pintype "bidirectional"))
    )
    (net (code "145") (name "P14.14") (class "Default")
      (node (ref "XMC4500") (pin "21") (pinfunction "P14.14_21") (pintype "bidirectional"))
    )
    (net (code "146") (name "P14.15") (class "Default")
      (node (ref "XMC4500") (pin "20") (pinfunction "P14.15_20") (pintype "bidirectional"))
    )
    (net (code "147") (name "P15.2") (class "Default")
      (node (ref "XMC4500") (pin "19") (pinfunction "P15.2_19") (pintype "bidirectional"))
    )
    (net (code "148") (name "P15.3") (class "Default")
      (node (ref "XMC4500") (pin "18") (pinfunction "P15.3_18") (pintype "bidirectional"))
    )
    (net (code "149") (name "P15.8") (class "Default")
      (node (ref "XMC4500") (pin "39") (pinfunction "P15.8_39") (pintype "bidirectional"))
    )
    (net (code "150") (name "P15.9") (class "Default")
      (node (ref "XMC4500") (pin "38") (pinfunction "P15.9_38") (pintype "bidirectional"))
    )
    (net (code "151") (name "PWM_MC1") (class "Default")
      (node (ref "IC1") (pin "7") (pinfunction "B1_7") (pintype "bidirectional"))
      (node (ref "R36") (pin "2") (pinfunction "2_2") (pintype "passive"))
    )
    (net (code "152") (name "PWM_MC2") (class "Default")
      (node (ref "IC1") (pin "6") (pinfunction "B2_6") (pintype "bidirectional"))
      (node (ref "R35") (pin "2") (pinfunction "2_2") (pintype "passive"))
    )
    (net (code "153") (name "PWM_MC3") (class "Default")
      (node (ref "IC2") (pin "7") (pinfunction "B1_7") (pintype "bidirectional"))
      (node (ref "R37") (pin "2") (pinfunction "2_2") (pintype "passive"))
    )
    (net (code "154") (name "PWM_MC4") (class "Default")
      (node (ref "IC2") (pin "6") (pinfunction "B2_6") (pintype "bidirectional"))
      (node (ref "R38") (pin "2") (pinfunction "2_2") (pintype "passive"))
    )
    (net (code "155") (name "RESET#") (class "Default")
      (node (ref "C20") (pin "1") (pinfunction "1_1") (pintype "passive"))
      (node (ref "D5") (pin "2") (pinfunction "A_2") (pintype "passive"))
      (node (ref "R1") (pin "1") (pinfunction "1_1") (pintype "passive"))
      (node (ref "SW1") (pin "P") (pinfunction "P_P") (pintype "passive"))
      (node (ref "SW1") (pin "P1") (pinfunction "P_P1") (pintype "passive"))
      (node (ref "XMC4500") (pin "65") (pinfunction "PORST#_65") (pintype "bidirectional"))
    )
    (net (code "156") (name "RTC1") (class "Default")
      (node (ref "XMC4500") (pin "15") (pinfunction "RTC_XTAL_1_15") (pintype "bidirectional"))
    )
    (net (code "157") (name "RTC2") (class "Default")
      (node (ref "XMC4500") (pin "16") (pinfunction "RTC_XTAL_2_16") (pintype "bidirectional"))
    )
    (net (code "158") (name "TCK") (class "Default")
      (node (ref "CON2") (pin "4") (pinfunction "4_4") (pintype "passive"))
      (node (ref "U201") (pin "22") (pinfunction "P2.4_22") (pintype "bidirectional"))
      (node (ref "U201") (pin "39") (pinfunction "P1.1_39") (pintype "bidirectional"))
      (node (ref "XMC4500") (pin "67") (pinfunction "TCK_67") (pintype "bidirectional"))
    )
    (net (code "159") (name "TMS") (class "Default")
      (node (ref "CON2") (pin "2") (pinfunction "2_2") (pintype "passive"))
      (node (ref "U201") (pin "35") (pinfunction "P1.5_35") (pintype "bidirectional"))
      (node (ref "U201") (pin "36") (pinfunction "P1.4_36") (pintype "bidirectional"))
      (node (ref "XMC4500") (pin "66") (pinfunction "TMS_66") (pintype "bidirectional"))
    )
    (net (code "160") (name "USB_D+") (class "Default")
      (node (ref "R11") (pin "2") (pinfunction "2_2") (pintype "passive"))
      (node (ref "XMC4500") (pin "9") (pinfunction "USB_D+_9") (pintype "bidirectional"))
    )
    (net (code "161") (name "USB_D-") (class "Default")
      (node (ref "R10") (pin "2") (pinfunction "2_2") (pintype "passive"))
      (node (ref "XMC4500") (pin "8") (pinfunction "USB_D-_8") (pintype "bidirectional"))
    )
    (net (code "162") (name "VAREF") (class "Default")
      (node (ref "C16") (pin "1") (pinfunction "1_1") (pintype "passive"))
      (node (ref "L2") (pin "1") (pinfunction "1_1") (pintype "passive"))
      (node (ref "XMC4500") (pin "33") (pinfunction "VAREF_33") (pintype "bidirectional"))
    )
    (net (code "163") (name "VBAT_IN") (class "Default")
      (node (ref "C25") (pin "1") (pinfunction "1_1") (pintype "passive"))
      (node (ref "C27") (pin "1") (pinfunction "1_1") (pintype "passive"))
      (node (ref "C32") (pin "1") (pinfunction "1_1") (pintype "passive"))
      (node (ref "C33") (pin "2") (pinfunction "2_2") (pintype "passive"))
      (node (ref "CON9") (pin "2") (pinfunction "2_2") (pintype "passive"))
      (node (ref "CON9") (pin "4") (pinfunction "4_4") (pintype "passive"))
      (node (ref "EL1") (pin "1") (pinfunction "1_1") (pintype "passive"))
      (node (ref "EL2") (pin "1") (pinfunction "1_1") (pintype "passive"))
      (node (ref "EL3") (pin "1") (pinfunction "1_1") (pintype "passive"))
      (node (ref "EL4") (pin "1") (pinfunction "1_1") (pintype "passive"))
      (node (ref "L4") (pin "P$2") (pinfunction "2_P$2") (pintype "bidirectional"))
      (node (ref "M1_OUT") (pin "10") (pinfunction "10_10") (pintype "passive"))
      (node (ref "M1_OUT") (pin "9") (pinfunction "9_9") (pintype "passive"))
      (node (ref "M2_OUT") (pin "10") (pinfunction "10_10") (pintype "passive"))
      (node (ref "M2_OUT") (pin "9") (pinfunction "9_9") (pintype "passive"))
      (node (ref "M3_OUT") (pin "10") (pinfunction "10_10") (pintype "passive"))
      (node (ref "M3_OUT") (pin "9") (pinfunction "9_9") (pintype "passive"))
      (node (ref "M4_OUT") (pin "10") (pinfunction "10_10") (pintype "passive"))
      (node (ref "M4_OUT") (pin "9") (pinfunction "9_9") (pintype "passive"))
      (node (ref "PAD1") (pin "P$1") (pinfunction "P$1_P$1") (pintype "bidirectional"))
      (node (ref "VREG1") (pin "7") (pinfunction "7_7") (pintype "bidirectional"))
    )
    (net (code "164") (name "VBUS") (class "Default")
      (node (ref "D2") (pin "A") (pinfunction "A_A") (pintype "passive"))
      (node (ref "L1") (pin "1") (pinfunction "1_1") (pintype "passive"))
      (node (ref "XMC4500") (pin "10") (pinfunction "VBUS_10") (pintype "bidirectional"))
    )
    (net (code "165") (name "VDD3.3") (class "Default")
      (node (ref "C1") (pin "1") (pinfunction "1_1") (pintype "passive"))
      (node (ref "C14") (pin "1") (pinfunction "1_1") (pintype "passive"))
      (node (ref "C15") (pin "2") (pinfunction "2_2") (pintype "passive"))
      (node (ref "C18") (pin "2") (pinfunction "2_2") (pintype "passive"))
      (node (ref "C2") (pin "1") (pinfunction "1_1") (pintype "passive"))
      (node (ref "C204") (pin "1") (pinfunction "1_1") (pintype "passive"))
      (node (ref "C21") (pin "2") (pinfunction "2_2") (pintype "passive"))
      (node (ref "C211") (pin "1") (pinfunction "1_1") (pintype "passive"))
      (node (ref "C212") (pin "1") (pinfunction "1_1") (pintype "passive"))
      (node (ref "C213") (pin "1") (pinfunction "1_1") (pintype "passive"))
      (node (ref "C23") (pin "1") (pinfunction "1_1") (pintype "passive"))
      (node (ref "C3") (pin "1") (pinfunction "1_1") (pintype "passive"))
      (node (ref "C37") (pin "1") (pinfunction "1_1") (pintype "passive"))
      (node (ref "C38") (pin "1") (pinfunction "1_1") (pintype "passive"))
      (node (ref "C4") (pin "1") (pinfunction "1_1") (pintype "passive"))
      (node (ref "C5") (pin "1") (pinfunction "1_1") (pintype "passive"))
      (node (ref "C6") (pin "1") (pinfunction "1_1") (pintype "passive"))
      (node (ref "CON10") (pin "3") (pinfunction "3_3") (pintype "passive"))
      (node (ref "CON12") (pin "1") (pinfunction "1_1") (pintype "passive"))
      (node (ref "CON15") (pin "1") (pinfunction "1_1") (pintype "passive"))
      (node (ref "CON2") (pin "1") (pinfunction "1_1") (pintype "passive"))
      (node (ref "CON3") (pin "2") (pinfunction "2_2") (pintype "passive"))
      (node (ref "CON4") (pin "1") (pinfunction "1_1") (pintype "passive"))
      (node (ref "D3") (pin "P$2") (pinfunction "P$2_P$2") (pintype "bidirectional"))
      (node (ref "DPS310") (pin "P6") (pinfunction "VDDIO_P6") (pintype "bidirectional"))
      (node (ref "DPS310") (pin "P8") (pinfunction "VDD_P8") (pintype "bidirectional"))
      (node (ref "IC1") (pin "1") (pinfunction "VCCA_1") (pintype "bidirectional"))
      (node (ref "IC1") (pin "5") (pinfunction "DIR_5") (pintype "bidirectional"))
      (node (ref "IC2") (pin "1") (pinfunction "VCCA_1") (pintype "bidirectional"))
      (node (ref "IC2") (pin "5") (pinfunction "DIR_5") (pintype "bidirectional"))
      (node (ref "L2") (pin "2") (pinfunction "2_2") (pintype "passive"))
      (node (ref "L3") (pin "2") (pinfunction "2_2") (pintype "passive"))
      (node (ref "M1_IN") (pin "3") (pinfunction "3_3") (pintype "passive"))
      (node (ref "M1_IN") (pin "4") (pinfunction "4_4") (pintype "passive"))
      (node (ref "M2_IN") (pin "3") (pinfunction "3_3") (pintype "passive"))
      (node (ref "M2_IN") (pin "4") (pinfunction "4_4") (pintype "passive"))
      (node (ref "M3_IN") (pin "3") (pinfunction "3_3") (pintype "passive"))
      (node (ref "M3_IN") (pin "4") (pinfunction "4_4") (pintype "passive"))
      (node (ref "M4_IN") (pin "3") (pinfunction "3_3") (pintype "passive"))
      (node (ref "M4_IN") (pin "4") (pinfunction "4_4") (pintype "passive"))
      (node (ref "MPU9250") (pin "1") (pinfunction "1_1") (pintype "bidirectional"))
      (node (ref "MPU9250") (pin "13") (pinfunction "13_13") (pintype "bidirectional"))
      (node (ref "MPU9250") (pin "22") (pinfunction "22_22") (pintype "bidirectional"))
      (node (ref "MPU9250") (pin "8") (pinfunction "8_8") (pintype "bidirectional"))
      (node (ref "R1") (pin "2") (pinfunction "2_2") (pintype "passive"))
      (node (ref "R14") (pin "2") (pinfunction "2_2") (pintype "passive"))
      (node (ref "R15") (pin "2") (pinfunction "2_2") (pintype "passive"))
      (node (ref "R16") (pin "1") (pinfunction "1_1") (pintype "passive"))
      (node (ref "R17") (pin "1") (pinfunction "1_1") (pintype "passive"))
      (node (ref "R2") (pin "1") (pinfunction "1_1") (pintype "passive"))
      (node (ref "R201") (pin "1") (pinfunction "1_1") (pintype "passive"))
      (node (ref "R202") (pin "1") (pinfunction "1_1") (pintype "passive"))
      (node (ref "R211") (pin "2") (pinfunction "2_2") (pintype "passive"))
      (node (ref "R4") (pin "1") (pinfunction "1_1") (pintype "passive"))
      (node (ref "R5") (pin "2") (pinfunction "2_2") (pintype "passive"))
      (node (ref "R8") (pin "1") (pinfunction "1_1") (pintype "passive"))
      (node (ref "R9") (pin "1") (pinfunction "1_1") (pintype "passive"))
      (node (ref "RN42") (pin "VDD") (pinfunction "11_VDD_VDD") (pintype "bidirectional"))
      (node (ref "U$9") (pin "P$1") (pinfunction "P$1_P$1") (pintype "bidirectional"))
      (node (ref "U201") (pin "10") (pinfunction "VBAT_10") (pintype "bidirectional"))
      (node (ref "U201") (pin "18") (pinfunction "VAREF_18") (pintype "bidirectional"))
      (node (ref "U201") (pin "28") (pinfunction "VDDP1_28") (pintype "bidirectional"))
      (node (ref "U201") (pin "41") (pinfunction "VDDP2_41") (pintype "bidirectional"))
      (node (ref "U201") (pin "5") (pinfunction "VDDP_5") (pintype "bidirectional"))
      (node (ref "VREG2") (pin "2") (pinfunction "OUT1_2") (pintype "power_in"))
      (node (ref "VREG2") (pin "4") (pinfunction "OUT2_4") (pintype "power_in"))
      (node (ref "XMC4500") (pin "11") (pinfunction "VDDP_11") (pintype "bidirectional"))
      (node (ref "XMC4500") (pin "17") (pinfunction "VBAT_17") (pintype "bidirectional"))
      (node (ref "XMC4500") (pin "43") (pinfunction "VDDP1_43") (pintype "bidirectional"))
      (node (ref "XMC4500") (pin "60") (pinfunction "VDDP2_60") (pintype "bidirectional"))
      (node (ref "XMC4500") (pin "87") (pinfunction "VDDP3_87") (pintype "bidirectional"))
    )
    (net (code "166") (name "VDD5") (class "Default")
      (node (ref "C22") (pin "1") (pinfunction "1_1") (pintype "passive"))
      (node (ref "C26") (pin "1") (pinfunction "1_1") (pintype "passive"))
      (node (ref "C35") (pin "1") (pinfunction "1_1") (pintype "passive"))
      (node (ref "CON14") (pin "1") (pinfunction "1_1") (pintype "passive"))
      (node (ref "D2") (pin "C") (pinfunction "C_C") (pintype "passive"))
      (node (ref "IC1") (pin "8") (pinfunction "VCCB_8") (pintype "bidirectional"))
      (node (ref "IC2") (pin "8") (pinfunction "VCCB_8") (pintype "bidirectional"))
      (node (ref "L5") (pin "P$2") (pinfunction "2_P$2") (pintype "bidirectional"))
      (node (ref "V203") (pin "C") (pinfunction "C_C") (pintype "passive"))
      (node (ref "VREG1") (pin "4") (pinfunction "4_4") (pintype "bidirectional"))
      (node (ref "VREG2") (pin "3") (pinfunction "IN_3") (pintype "power_in"))
    )
    (net (code "167") (name "VDDA") (class "Default")
      (node (ref "C17") (pin "1") (pinfunction "1_1") (pintype "passive"))
      (node (ref "L3") (pin "1") (pinfunction "1_1") (pintype "passive"))
      (node (ref "XMC4500") (pin "35") (pinfunction "VDDA_35") (pintype "bidirectional"))
    )
    (net (code "168") (name "VDDC") (class "Default")
      (node (ref "C10") (pin "1") (pinfunction "1_1") (pintype "passive"))
      (node (ref "C11") (pin "1") (pinfunction "1_1") (pintype "passive"))
      (node (ref "C7") (pin "1") (pinfunction "1_1") (pintype "passive"))
      (node (ref "C8") (pin "1") (pinfunction "1_1") (pintype "passive"))
      (node (ref "C9") (pin "1") (pinfunction "1_1") (pintype "passive"))
      (node (ref "XMC4500") (pin "12") (pinfunction "VDDC_12") (pintype "bidirectional"))
      (node (ref "XMC4500") (pin "42") (pinfunction "VDDC1_42") (pintype "bidirectional"))
      (node (ref "XMC4500") (pin "64") (pinfunction "VDDC2_64") (pintype "bidirectional"))
      (node (ref "XMC4500") (pin "86") (pinfunction "VDDC3_86") (pintype "bidirectional"))
    )
    (net (code "169") (name "WTCK") (class "Default")
      (node (ref "U$9") (pin "P$2") (pinfunction "P$2_P$2") (pintype "bidirectional"))
      (node (ref "U201") (pin "34") (pinfunction "TCK_34") (pintype "bidirectional"))
    )
    (net (code "170") (name "WTMS") (class "Default")
      (node (ref "U$9") (pin "P$3") (pinfunction "P$3_P$3") (pintype "bidirectional"))
      (node (ref "U201") (pin "33") (pinfunction "TMS_33") (pintype "bidirectional"))
    )
    (net (code "171") (name "unconnected-(CON2-Pad7)") (class "Default")
      (node (ref "CON2") (pin "7") (pinfunction "7_7") (pintype "passive"))
    )
    (net (code "172") (name "unconnected-(DPS310-CSB-PadP2)") (class "Default")
      (node (ref "DPS310") (pin "P2") (pinfunction "CSB_P2") (pintype "bidirectional"))
    )
    (net (code "173") (name "unconnected-(MPU9250-Pad2)") (class "Default")
      (node (ref "MPU9250") (pin "2") (pinfunction "2_2") (pintype "bidirectional"))
    )
    (net (code "174") (name "unconnected-(MPU9250-Pad3)") (class "Default")
      (node (ref "MPU9250") (pin "3") (pinfunction "3_3") (pintype "bidirectional"))
    )
    (net (code "175") (name "unconnected-(MPU9250-Pad4)") (class "Default")
      (node (ref "MPU9250") (pin "4") (pinfunction "4_4") (pintype "bidirectional"))
    )
    (net (code "176") (name "unconnected-(MPU9250-Pad5)") (class "Default")
      (node (ref "MPU9250") (pin "5") (pinfunction "5_5") (pintype "bidirectional"))
    )
    (net (code "177") (name "unconnected-(MPU9250-Pad6)") (class "Default")
      (node (ref "MPU9250") (pin "6") (pinfunction "6_6") (pintype "bidirectional"))
    )
    (net (code "178") (name "unconnected-(MPU9250-Pad7)") (class "Default")
      (node (ref "MPU9250") (pin "7") (pinfunction "7_7") (pintype "bidirectional"))
    )
    (net (code "179") (name "unconnected-(MPU9250-Pad9)") (class "Default")
      (node (ref "MPU9250") (pin "9") (pinfunction "9_9") (pintype "bidirectional"))
    )
    (net (code "180") (name "unconnected-(MPU9250-Pad14)") (class "Default")
      (node (ref "MPU9250") (pin "14") (pinfunction "14_14") (pintype "bidirectional"))
    )
    (net (code "181") (name "unconnected-(MPU9250-Pad15)") (class "Default")
      (node (ref "MPU9250") (pin "15") (pinfunction "15_15") (pintype "bidirectional"))
    )
    (net (code "182") (name "unconnected-(MPU9250-Pad16)") (class "Default")
      (node (ref "MPU9250") (pin "16") (pinfunction "16_16") (pintype "bidirectional"))
    )
    (net (code "183") (name "unconnected-(MPU9250-Pad17)") (class "Default")
      (node (ref "MPU9250") (pin "17") (pinfunction "17_17") (pintype "bidirectional"))
    )
    (net (code "184") (name "unconnected-(MPU9250-Pad19)") (class "Default")
      (node (ref "MPU9250") (pin "19") (pinfunction "19_19") (pintype "bidirectional"))
    )
    (net (code "185") (name "unconnected-(MPU9250-Pad21)") (class "Default")
      (node (ref "MPU9250") (pin "21") (pinfunction "21_21") (pintype "bidirectional"))
    )
    (net (code "186") (name "unconnected-(U201-P0.0-Pad2)") (class "Default")
      (node (ref "U201") (pin "2") (pinfunction "P0.0_2") (pintype "bidirectional"))
    )
    (net (code "187") (name "unconnected-(U201-P0.3-Pad47)") (class "Default")
      (node (ref "U201") (pin "47") (pinfunction "P0.3_47") (pintype "bidirectional"))
    )
    (net (code "188") (name "unconnected-(U201-P0.6-Pad44)") (class "Default")
      (node (ref "U201") (pin "44") (pinfunction "P0.6_44") (pintype "bidirectional"))
    )
    (net (code "189") (name "unconnected-(U201-P0.7-Pad43)") (class "Default")
      (node (ref "U201") (pin "43") (pinfunction "P0.7_43") (pintype "bidirectional"))
    )
    (net (code "190") (name "unconnected-(U201-P0.8-Pad42)") (class "Default")
      (node (ref "U201") (pin "42") (pinfunction "P0.8_42") (pintype "bidirectional"))
    )
    (net (code "191") (name "unconnected-(U201-P1.2-Pad38)") (class "Default")
      (node (ref "U201") (pin "38") (pinfunction "P1.2_38") (pintype "bidirectional"))
    )
    (net (code "192") (name "unconnected-(U201-P1.3-Pad37)") (class "Default")
      (node (ref "U201") (pin "37") (pinfunction "P1.3_37") (pintype "bidirectional"))
    )
    (net (code "193") (name "unconnected-(U201-P2.0-Pad26)") (class "Default")
      (node (ref "U201") (pin "26") (pinfunction "P2.0_26") (pintype "bidirectional"))
    )
    (net (code "194") (name "unconnected-(U201-P2.1-Pad25)") (class "Default")
      (node (ref "U201") (pin "25") (pinfunction "P2.1_25") (pintype "bidirectional"))
    )
    (net (code "195") (name "unconnected-(U201-P2.2-Pad24)") (class "Default")
      (node (ref "U201") (pin "24") (pinfunction "P2.2_24") (pintype "bidirectional"))
    )
    (net (code "196") (name "unconnected-(U201-P2.5-Pad21)") (class "Default")
      (node (ref "U201") (pin "21") (pinfunction "P2.5_21") (pintype "bidirectional"))
    )
    (net (code "197") (name "unconnected-(U201-P14.0-Pad16)") (class "Default")
      (node (ref "U201") (pin "16") (pinfunction "P14.0_16") (pintype "bidirectional"))
    )
    (net (code "198") (name "unconnected-(U201-P14.3-Pad15)") (class "Default")
      (node (ref "U201") (pin "15") (pinfunction "P14.3_15") (pintype "bidirectional"))
    )
    (net (code "199") (name "unconnected-(U201-P14.9-Pad19)") (class "Default")
      (node (ref "U201") (pin "19") (pinfunction "P14.9_19") (pintype "bidirectional"))
    )
    (net (code "200") (name "unconnected-(U201-RTC_XTAL_1-Pad8)") (class "Default")
      (node (ref "U201") (pin "8") (pinfunction "RTC_XTAL_1_8") (pintype "bidirectional"))
    )
    (net (code "201") (name "unconnected-(U201-RTC_XTAL_2-Pad9)") (class "Default")
      (node (ref "U201") (pin "9") (pinfunction "RTC_XTAL_2_9") (pintype "bidirectional"))
    )
    (net (code "202") (name "unconnected-(USB-PGH1-PadP$1)") (class "Default")
      (node (ref "USB") (pin "P$1") (pinfunction "PGH1_P$1") (pintype "bidirectional"))
    )
    (net (code "203") (name "unconnected-(USB-PGH2-PadP$2)") (class "Default")
      (node (ref "USB") (pin "P$2") (pinfunction "PGH2_P$2") (pintype "bidirectional"))
    )
    (net (code "204") (name "unconnected-(USB-PGH3-PadP$3)") (class "Default")
      (node (ref "USB") (pin "P$3") (pinfunction "PGH3_P$3") (pintype "bidirectional"))
    )
    (net (code "205") (name "unconnected-(USB-PGH4-PadP$4)") (class "Default")
      (node (ref "USB") (pin "P$4") (pinfunction "PGH4_P$4") (pintype "bidirectional"))
    )
    (net (code "206") (name "unconnected-(USB-Pad2)") (class "Default")
      (node (ref "USB") (pin "2") (pinfunction "2_2") (pintype "passive"))
    )
    (net (code "207") (name "unconnected-(USB1-PGH1-PadP$1)") (class "Default")
      (node (ref "USB1") (pin "P$1") (pinfunction "PGH1_P$1") (pintype "bidirectional"))
    )
    (net (code "208") (name "unconnected-(USB1-PGH2-PadP$2)") (class "Default")
      (node (ref "USB1") (pin "P$2") (pinfunction "PGH2_P$2") (pintype "bidirectional"))
    )
    (net (code "209") (name "unconnected-(USB1-PGH3-PadP$3)") (class "Default")
      (node (ref "USB1") (pin "P$3") (pinfunction "PGH3_P$3") (pintype "bidirectional"))
    )
    (net (code "210") (name "unconnected-(USB1-PGH4-PadP$4)") (class "Default")
      (node (ref "USB1") (pin "P$4") (pinfunction "PGH4_P$4") (pintype "bidirectional"))
    )
    (net (code "211") (name "unconnected-(USB1-Pad2)") (class "Default")
      (node (ref "USB1") (pin "2") (pinfunction "2_2") (pintype "passive"))
    )
  )
)
